# FPGA_Power.net
KiCad netlist of a schematic drawn in Altium Designer
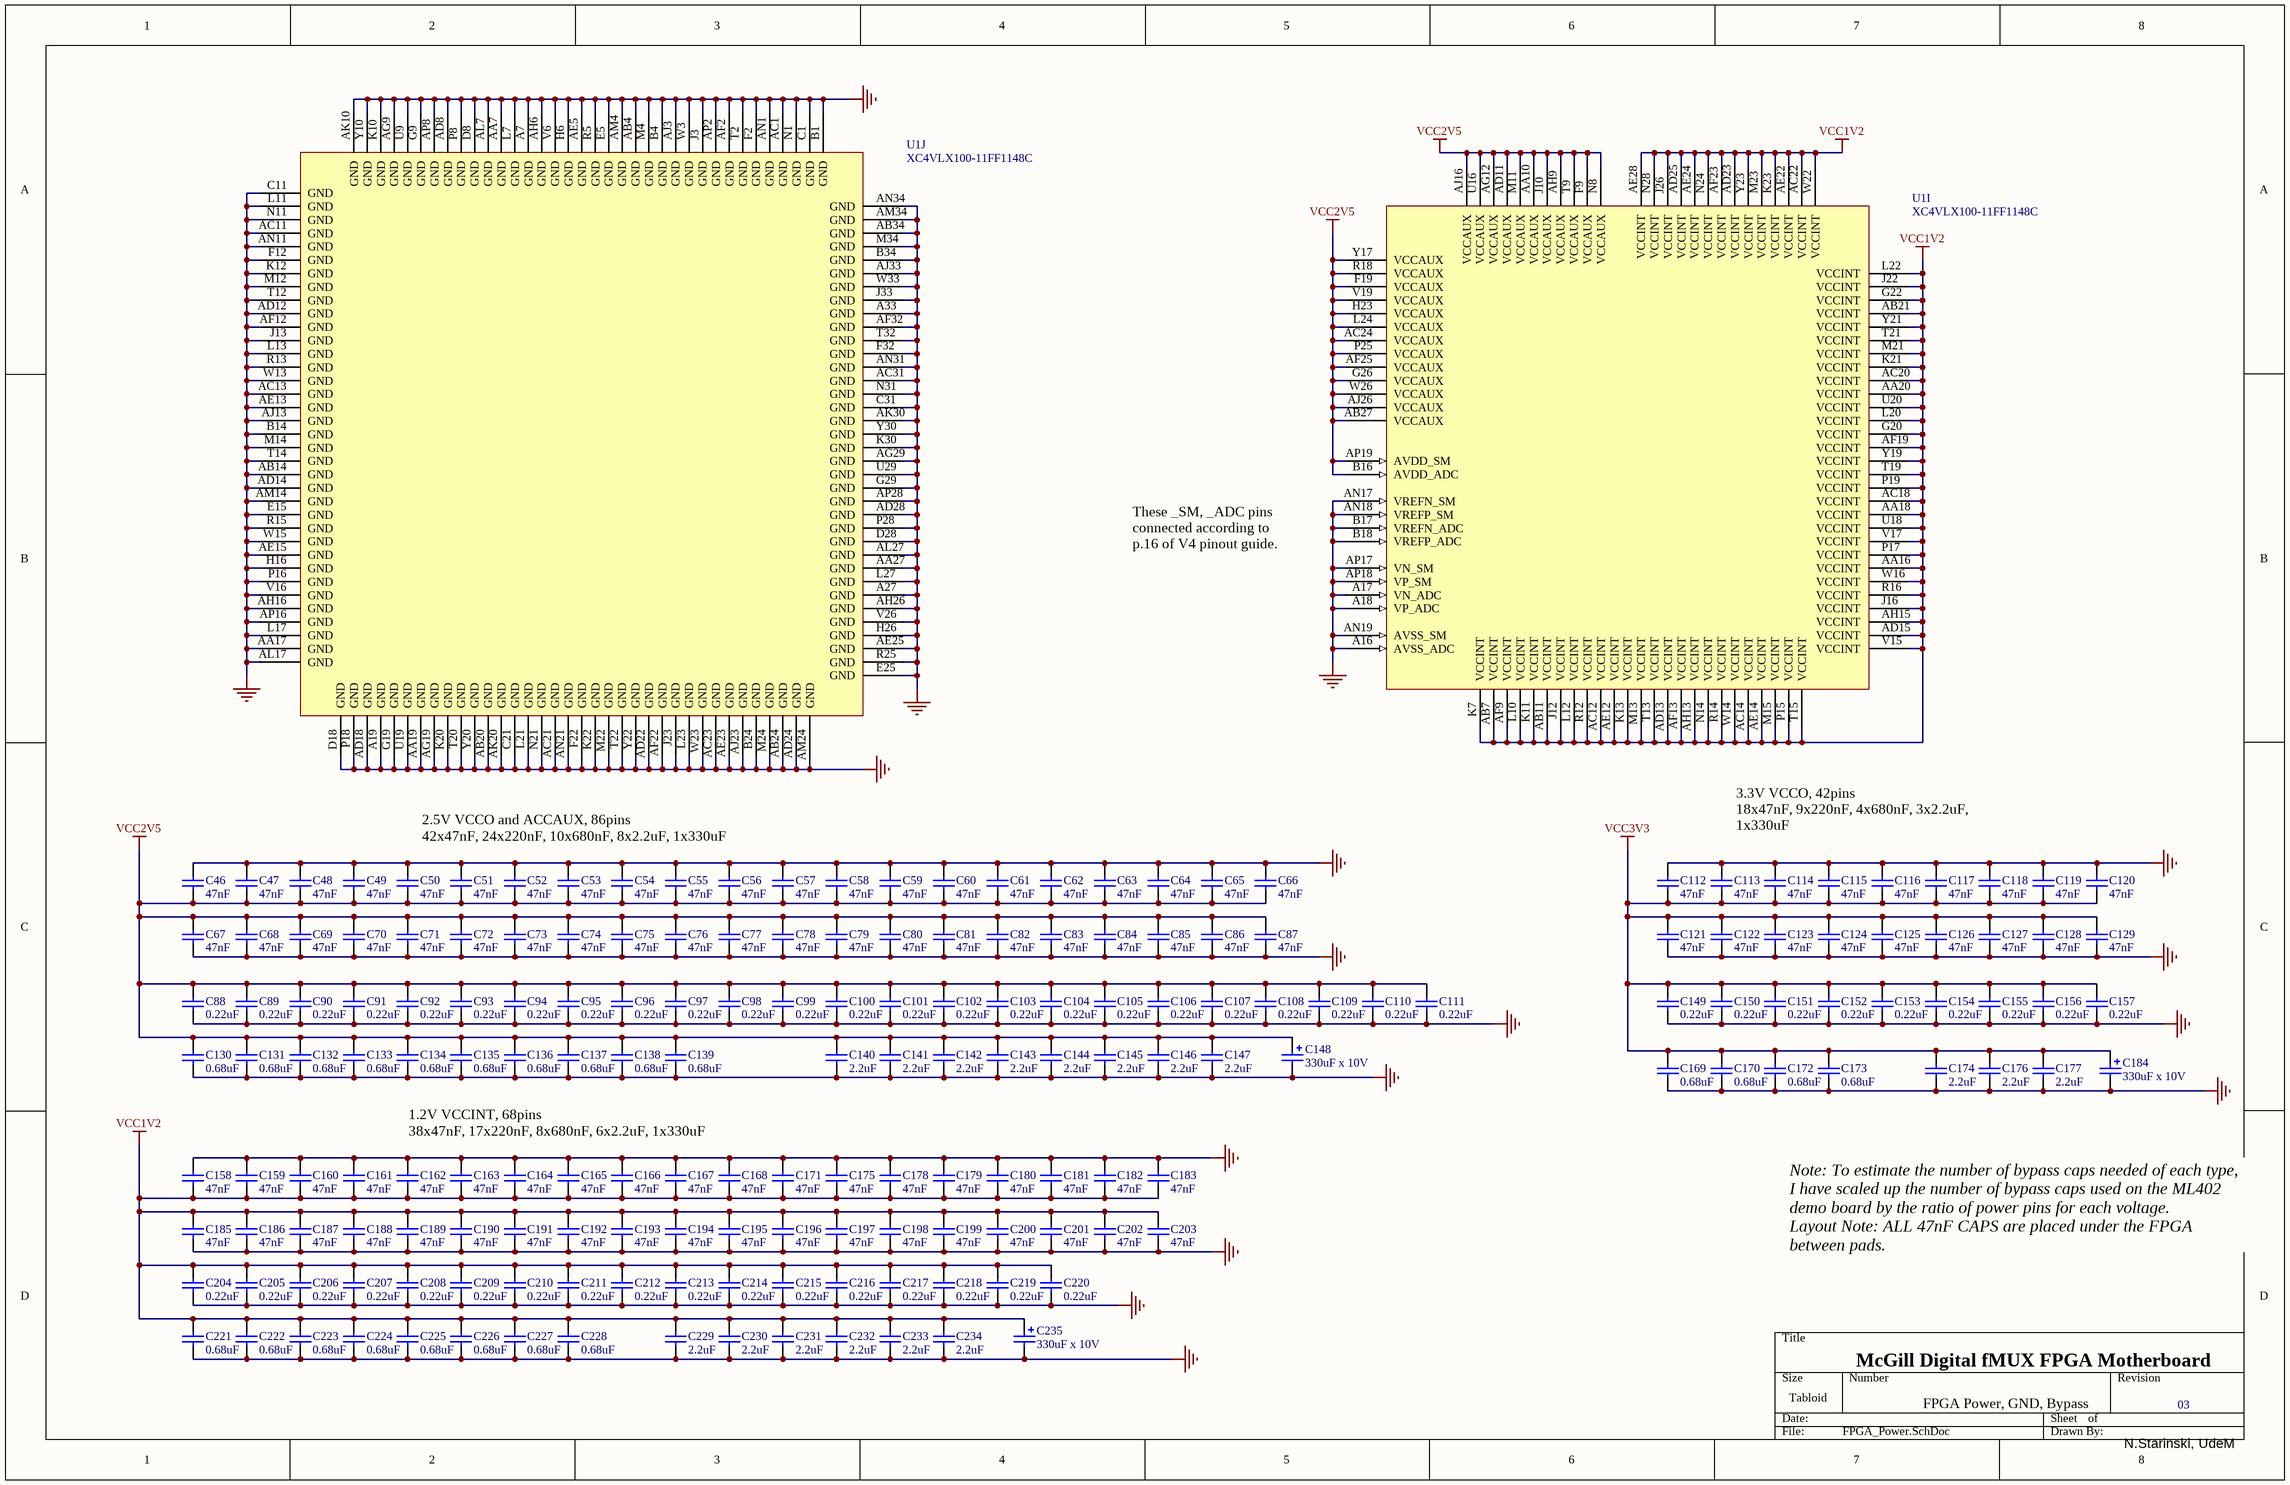
[diagram p0: FPGA_Power.SchDoc]

(export (version "E")
  (design (tool "Eeschema 10.0.6"))
  (components
    (comp (ref "C46")
      (value "47nF")
      (footprint "CC1005-0402")
      (description "Capacitor (Semiconductor SIM Model)")
      (fields (field (name "PUBLISHER") "Altium Limited"))
      (libsource (lib "Miscellaneous Devices") (part "Cap Semi"))
    )
    (comp (ref "C47")
      (value "47nF")
      (footprint "CC1005-0402")
      (description "Capacitor (Semiconductor SIM Model)")
      (fields (field (name "PUBLISHER") "Altium Limited"))
      (libsource (lib "Miscellaneous Devices") (part "Cap Semi"))
    )
    (comp (ref "C48")
      (value "47nF")
      (footprint "CC1005-0402")
      (description "Capacitor (Semiconductor SIM Model)")
      (fields (field (name "PUBLISHER") "Altium Limited"))
      (libsource (lib "Miscellaneous Devices") (part "Cap Semi"))
    )
    (comp (ref "C49")
      (value "47nF")
      (footprint "CC1005-0402")
      (description "Capacitor (Semiconductor SIM Model)")
      (fields (field (name "PUBLISHER") "Altium Limited"))
      (libsource (lib "Miscellaneous Devices") (part "Cap Semi"))
    )
    (comp (ref "C50")
      (value "47nF")
      (footprint "CC1005-0402")
      (description "Capacitor (Semiconductor SIM Model)")
      (fields (field (name "PUBLISHER") "Altium Limited"))
      (libsource (lib "Miscellaneous Devices") (part "Cap Semi"))
    )
    (comp (ref "C51")
      (value "47nF")
      (footprint "CC1005-0402")
      (description "Capacitor (Semiconductor SIM Model)")
      (fields (field (name "PUBLISHER") "Altium Limited"))
      (libsource (lib "Miscellaneous Devices") (part "Cap Semi"))
    )
    (comp (ref "C52")
      (value "47nF")
      (footprint "CC1005-0402")
      (description "Capacitor (Semiconductor SIM Model)")
      (fields (field (name "PUBLISHER") "Altium Limited"))
      (libsource (lib "Miscellaneous Devices") (part "Cap Semi"))
    )
    (comp (ref "C53")
      (value "47nF")
      (footprint "CC1005-0402")
      (description "Capacitor (Semiconductor SIM Model)")
      (fields (field (name "PUBLISHER") "Altium Limited"))
      (libsource (lib "Miscellaneous Devices") (part "Cap Semi"))
    )
    (comp (ref "C54")
      (value "47nF")
      (footprint "CC1005-0402")
      (description "Capacitor (Semiconductor SIM Model)")
      (fields (field (name "PUBLISHER") "Altium Limited"))
      (libsource (lib "Miscellaneous Devices") (part "Cap Semi"))
    )
    (comp (ref "C55")
      (value "47nF")
      (footprint "CC1005-0402")
      (description "Capacitor (Semiconductor SIM Model)")
      (fields (field (name "PUBLISHER") "Altium Limited"))
      (libsource (lib "Miscellaneous Devices") (part "Cap Semi"))
    )
    (comp (ref "C56")
      (value "47nF")
      (footprint "CC1005-0402")
      (description "Capacitor (Semiconductor SIM Model)")
      (fields (field (name "PUBLISHER") "Altium Limited"))
      (libsource (lib "Miscellaneous Devices") (part "Cap Semi"))
    )
    (comp (ref "C57")
      (value "47nF")
      (footprint "CC1005-0402")
      (description "Capacitor (Semiconductor SIM Model)")
      (fields (field (name "PUBLISHER") "Altium Limited"))
      (libsource (lib "Miscellaneous Devices") (part "Cap Semi"))
    )
    (comp (ref "C58")
      (value "47nF")
      (footprint "CC1005-0402")
      (description "Capacitor (Semiconductor SIM Model)")
      (fields (field (name "PUBLISHER") "Altium Limited"))
      (libsource (lib "Miscellaneous Devices") (part "Cap Semi"))
    )
    (comp (ref "C59")
      (value "47nF")
      (footprint "CC1005-0402")
      (description "Capacitor (Semiconductor SIM Model)")
      (fields (field (name "PUBLISHER") "Altium Limited"))
      (libsource (lib "Miscellaneous Devices") (part "Cap Semi"))
    )
    (comp (ref "C60")
      (value "47nF")
      (footprint "CC1005-0402")
      (description "Capacitor (Semiconductor SIM Model)")
      (fields (field (name "PUBLISHER") "Altium Limited"))
      (libsource (lib "Miscellaneous Devices") (part "Cap Semi"))
    )
    (comp (ref "C61")
      (value "47nF")
      (footprint "CC1005-0402")
      (description "Capacitor (Semiconductor SIM Model)")
      (fields (field (name "PUBLISHER") "Altium Limited"))
      (libsource (lib "Miscellaneous Devices") (part "Cap Semi"))
    )
    (comp (ref "C62")
      (value "47nF")
      (footprint "CC1005-0402")
      (description "Capacitor (Semiconductor SIM Model)")
      (fields (field (name "PUBLISHER") "Altium Limited"))
      (libsource (lib "Miscellaneous Devices") (part "Cap Semi"))
    )
    (comp (ref "C63")
      (value "47nF")
      (footprint "CC1005-0402")
      (description "Capacitor (Semiconductor SIM Model)")
      (fields (field (name "PUBLISHER") "Altium Limited"))
      (libsource (lib "Miscellaneous Devices") (part "Cap Semi"))
    )
    (comp (ref "C64")
      (value "47nF")
      (footprint "CC1005-0402")
      (description "Capacitor (Semiconductor SIM Model)")
      (fields (field (name "PUBLISHER") "Altium Limited"))
      (libsource (lib "Miscellaneous Devices") (part "Cap Semi"))
    )
    (comp (ref "C65")
      (value "47nF")
      (footprint "CC1005-0402")
      (description "Capacitor (Semiconductor SIM Model)")
      (fields (field (name "PUBLISHER") "Altium Limited"))
      (libsource (lib "Miscellaneous Devices") (part "Cap Semi"))
    )
    (comp (ref "C66")
      (value "47nF")
      (footprint "CC1005-0402")
      (description "Capacitor (Semiconductor SIM Model)")
      (fields (field (name "PUBLISHER") "Altium Limited"))
      (libsource (lib "Miscellaneous Devices") (part "Cap Semi"))
    )
    (comp (ref "C67")
      (value "47nF")
      (footprint "CC1005-0402")
      (description "Capacitor (Semiconductor SIM Model)")
      (fields (field (name "PUBLISHER") "Altium Limited"))
      (libsource (lib "Miscellaneous Devices") (part "Cap Semi"))
    )
    (comp (ref "C68")
      (value "47nF")
      (footprint "CC1005-0402")
      (description "Capacitor (Semiconductor SIM Model)")
      (fields (field (name "PUBLISHER") "Altium Limited"))
      (libsource (lib "Miscellaneous Devices") (part "Cap Semi"))
    )
    (comp (ref "C69")
      (value "47nF")
      (footprint "CC1005-0402")
      (description "Capacitor (Semiconductor SIM Model)")
      (fields (field (name "PUBLISHER") "Altium Limited"))
      (libsource (lib "Miscellaneous Devices") (part "Cap Semi"))
    )
    (comp (ref "C70")
      (value "47nF")
      (footprint "CC1005-0402")
      (description "Capacitor (Semiconductor SIM Model)")
      (fields (field (name "PUBLISHER") "Altium Limited"))
      (libsource (lib "Miscellaneous Devices") (part "Cap Semi"))
    )
    (comp (ref "C71")
      (value "47nF")
      (footprint "CC1005-0402")
      (description "Capacitor (Semiconductor SIM Model)")
      (fields (field (name "PUBLISHER") "Altium Limited"))
      (libsource (lib "Miscellaneous Devices") (part "Cap Semi"))
    )
    (comp (ref "C72")
      (value "47nF")
      (footprint "CC1005-0402")
      (description "Capacitor (Semiconductor SIM Model)")
      (fields (field (name "PUBLISHER") "Altium Limited"))
      (libsource (lib "Miscellaneous Devices") (part "Cap Semi"))
    )
    (comp (ref "C73")
      (value "47nF")
      (footprint "CC1005-0402")
      (description "Capacitor (Semiconductor SIM Model)")
      (fields (field (name "PUBLISHER") "Altium Limited"))
      (libsource (lib "Miscellaneous Devices") (part "Cap Semi"))
    )
    (comp (ref "C74")
      (value "47nF")
      (footprint "CC1005-0402")
      (description "Capacitor (Semiconductor SIM Model)")
      (fields (field (name "PUBLISHER") "Altium Limited"))
      (libsource (lib "Miscellaneous Devices") (part "Cap Semi"))
    )
    (comp (ref "C75")
      (value "47nF")
      (footprint "CC1005-0402")
      (description "Capacitor (Semiconductor SIM Model)")
      (fields (field (name "PUBLISHER") "Altium Limited"))
      (libsource (lib "Miscellaneous Devices") (part "Cap Semi"))
    )
    (comp (ref "C76")
      (value "47nF")
      (footprint "CC1005-0402")
      (description "Capacitor (Semiconductor SIM Model)")
      (fields (field (name "PUBLISHER") "Altium Limited"))
      (libsource (lib "Miscellaneous Devices") (part "Cap Semi"))
    )
    (comp (ref "C77")
      (value "47nF")
      (footprint "CC1005-0402")
      (description "Capacitor (Semiconductor SIM Model)")
      (fields (field (name "PUBLISHER") "Altium Limited"))
      (libsource (lib "Miscellaneous Devices") (part "Cap Semi"))
    )
    (comp (ref "C78")
      (value "47nF")
      (footprint "CC1005-0402")
      (description "Capacitor (Semiconductor SIM Model)")
      (fields (field (name "PUBLISHER") "Altium Limited"))
      (libsource (lib "Miscellaneous Devices") (part "Cap Semi"))
    )
    (comp (ref "C79")
      (value "47nF")
      (footprint "CC1005-0402")
      (description "Capacitor (Semiconductor SIM Model)")
      (fields (field (name "PUBLISHER") "Altium Limited"))
      (libsource (lib "Miscellaneous Devices") (part "Cap Semi"))
    )
    (comp (ref "C80")
      (value "47nF")
      (footprint "CC1005-0402")
      (description "Capacitor (Semiconductor SIM Model)")
      (fields (field (name "PUBLISHER") "Altium Limited"))
      (libsource (lib "Miscellaneous Devices") (part "Cap Semi"))
    )
    (comp (ref "C81")
      (value "47nF")
      (footprint "CC1005-0402")
      (description "Capacitor (Semiconductor SIM Model)")
      (fields (field (name "PUBLISHER") "Altium Limited"))
      (libsource (lib "Miscellaneous Devices") (part "Cap Semi"))
    )
    (comp (ref "C82")
      (value "47nF")
      (footprint "CC1005-0402")
      (description "Capacitor (Semiconductor SIM Model)")
      (fields (field (name "PUBLISHER") "Altium Limited"))
      (libsource (lib "Miscellaneous Devices") (part "Cap Semi"))
    )
    (comp (ref "C83")
      (value "47nF")
      (footprint "CC1005-0402")
      (description "Capacitor (Semiconductor SIM Model)")
      (fields (field (name "PUBLISHER") "Altium Limited"))
      (libsource (lib "Miscellaneous Devices") (part "Cap Semi"))
    )
    (comp (ref "C84")
      (value "47nF")
      (footprint "CC1005-0402")
      (description "Capacitor (Semiconductor SIM Model)")
      (fields (field (name "PUBLISHER") "Altium Limited"))
      (libsource (lib "Miscellaneous Devices") (part "Cap Semi"))
    )
    (comp (ref "C85")
      (value "47nF")
      (footprint "CC1005-0402")
      (description "Capacitor (Semiconductor SIM Model)")
      (fields (field (name "PUBLISHER") "Altium Limited"))
      (libsource (lib "Miscellaneous Devices") (part "Cap Semi"))
    )
    (comp (ref "C86")
      (value "47nF")
      (footprint "CC1005-0402")
      (description "Capacitor (Semiconductor SIM Model)")
      (fields (field (name "PUBLISHER") "Altium Limited"))
      (libsource (lib "Miscellaneous Devices") (part "Cap Semi"))
    )
    (comp (ref "C87")
      (value "47nF")
      (footprint "CC1005-0402")
      (description "Capacitor (Semiconductor SIM Model)")
      (fields (field (name "PUBLISHER") "Altium Limited"))
      (libsource (lib "Miscellaneous Devices") (part "Cap Semi"))
    )
    (comp (ref "C88")
      (value "0.22uF")
      (footprint "CC1608-0603")
      (description "Capacitor (Semiconductor SIM Model)")
      (fields (field (name "PUBLISHER") "Altium Limited"))
      (libsource (lib "Miscellaneous Devices") (part "Cap Semi"))
    )
    (comp (ref "C89")
      (value "0.22uF")
      (footprint "CC1608-0603")
      (description "Capacitor (Semiconductor SIM Model)")
      (fields (field (name "PUBLISHER") "Altium Limited"))
      (libsource (lib "Miscellaneous Devices") (part "Cap Semi"))
    )
    (comp (ref "C90")
      (value "0.22uF")
      (footprint "CC1608-0603")
      (description "Capacitor (Semiconductor SIM Model)")
      (fields (field (name "PUBLISHER") "Altium Limited"))
      (libsource (lib "Miscellaneous Devices") (part "Cap Semi"))
    )
    (comp (ref "C91")
      (value "0.22uF")
      (footprint "CC1608-0603")
      (description "Capacitor (Semiconductor SIM Model)")
      (fields (field (name "PUBLISHER") "Altium Limited"))
      (libsource (lib "Miscellaneous Devices") (part "Cap Semi"))
    )
    (comp (ref "C92")
      (value "0.22uF")
      (footprint "CC1608-0603")
      (description "Capacitor (Semiconductor SIM Model)")
      (fields (field (name "PUBLISHER") "Altium Limited"))
      (libsource (lib "Miscellaneous Devices") (part "Cap Semi"))
    )
    (comp (ref "C93")
      (value "0.22uF")
      (footprint "CC1608-0603")
      (description "Capacitor (Semiconductor SIM Model)")
      (fields (field (name "PUBLISHER") "Altium Limited"))
      (libsource (lib "Miscellaneous Devices") (part "Cap Semi"))
    )
    (comp (ref "C94")
      (value "0.22uF")
      (footprint "CC1608-0603")
      (description "Capacitor (Semiconductor SIM Model)")
      (fields (field (name "PUBLISHER") "Altium Limited"))
      (libsource (lib "Miscellaneous Devices") (part "Cap Semi"))
    )
    (comp (ref "C95")
      (value "0.22uF")
      (footprint "CC1608-0603")
      (description "Capacitor (Semiconductor SIM Model)")
      (fields (field (name "PUBLISHER") "Altium Limited"))
      (libsource (lib "Miscellaneous Devices") (part "Cap Semi"))
    )
    (comp (ref "C96")
      (value "0.22uF")
      (footprint "CC1608-0603")
      (description "Capacitor (Semiconductor SIM Model)")
      (fields (field (name "PUBLISHER") "Altium Limited"))
      (libsource (lib "Miscellaneous Devices") (part "Cap Semi"))
    )
    (comp (ref "C97")
      (value "0.22uF")
      (footprint "CC1608-0603")
      (description "Capacitor (Semiconductor SIM Model)")
      (fields (field (name "PUBLISHER") "Altium Limited"))
      (libsource (lib "Miscellaneous Devices") (part "Cap Semi"))
    )
    (comp (ref "C98")
      (value "0.22uF")
      (footprint "CC1608-0603")
      (description "Capacitor (Semiconductor SIM Model)")
      (fields (field (name "PUBLISHER") "Altium Limited"))
      (libsource (lib "Miscellaneous Devices") (part "Cap Semi"))
    )
    (comp (ref "C99")
      (value "0.22uF")
      (footprint "CC1608-0603")
      (description "Capacitor (Semiconductor SIM Model)")
      (fields (field (name "PUBLISHER") "Altium Limited"))
      (libsource (lib "Miscellaneous Devices") (part "Cap Semi"))
    )
    (comp (ref "C100")
      (value "0.22uF")
      (footprint "CC1608-0603")
      (description "Capacitor (Semiconductor SIM Model)")
      (fields (field (name "PUBLISHER") "Altium Limited"))
      (libsource (lib "Miscellaneous Devices") (part "Cap Semi"))
    )
    (comp (ref "C101")
      (value "0.22uF")
      (footprint "CC1608-0603")
      (description "Capacitor (Semiconductor SIM Model)")
      (fields (field (name "PUBLISHER") "Altium Limited"))
      (libsource (lib "Miscellaneous Devices") (part "Cap Semi"))
    )
    (comp (ref "C102")
      (value "0.22uF")
      (footprint "CC1608-0603")
      (description "Capacitor (Semiconductor SIM Model)")
      (fields (field (name "PUBLISHER") "Altium Limited"))
      (libsource (lib "Miscellaneous Devices") (part "Cap Semi"))
    )
    (comp (ref "C103")
      (value "0.22uF")
      (footprint "CC1608-0603")
      (description "Capacitor (Semiconductor SIM Model)")
      (fields (field (name "PUBLISHER") "Altium Limited"))
      (libsource (lib "Miscellaneous Devices") (part "Cap Semi"))
    )
    (comp (ref "C104")
      (value "0.22uF")
      (footprint "CC1608-0603")
      (description "Capacitor (Semiconductor SIM Model)")
      (fields (field (name "PUBLISHER") "Altium Limited"))
      (libsource (lib "Miscellaneous Devices") (part "Cap Semi"))
    )
    (comp (ref "C105")
      (value "0.22uF")
      (footprint "CC1608-0603")
      (description "Capacitor (Semiconductor SIM Model)")
      (fields (field (name "PUBLISHER") "Altium Limited"))
      (libsource (lib "Miscellaneous Devices") (part "Cap Semi"))
    )
    (comp (ref "C106")
      (value "0.22uF")
      (footprint "CC1608-0603")
      (description "Capacitor (Semiconductor SIM Model)")
      (fields (field (name "PUBLISHER") "Altium Limited"))
      (libsource (lib "Miscellaneous Devices") (part "Cap Semi"))
    )
    (comp (ref "C107")
      (value "0.22uF")
      (footprint "CC1608-0603")
      (description "Capacitor (Semiconductor SIM Model)")
      (fields (field (name "PUBLISHER") "Altium Limited"))
      (libsource (lib "Miscellaneous Devices") (part "Cap Semi"))
    )
    (comp (ref "C108")
      (value "0.22uF")
      (footprint "CC1608-0603")
      (description "Capacitor (Semiconductor SIM Model)")
      (fields (field (name "PUBLISHER") "Altium Limited"))
      (libsource (lib "Miscellaneous Devices") (part "Cap Semi"))
    )
    (comp (ref "C109")
      (value "0.22uF")
      (footprint "CC1608-0603")
      (description "Capacitor (Semiconductor SIM Model)")
      (fields (field (name "PUBLISHER") "Altium Limited"))
      (libsource (lib "Miscellaneous Devices") (part "Cap Semi"))
    )
    (comp (ref "C110")
      (value "0.22uF")
      (footprint "CC1608-0603")
      (description "Capacitor (Semiconductor SIM Model)")
      (fields (field (name "PUBLISHER") "Altium Limited"))
      (libsource (lib "Miscellaneous Devices") (part "Cap Semi"))
    )
    (comp (ref "C111")
      (value "0.22uF")
      (footprint "CC1608-0603")
      (description "Capacitor (Semiconductor SIM Model)")
      (fields (field (name "PUBLISHER") "Altium Limited"))
      (libsource (lib "Miscellaneous Devices") (part "Cap Semi"))
    )
    (comp (ref "C112")
      (value "47nF")
      (footprint "CC1005-0402")
      (description "Capacitor (Semiconductor SIM Model)")
      (fields (field (name "PUBLISHER") "Altium Limited"))
      (libsource (lib "Miscellaneous Devices") (part "Cap Semi"))
    )
    (comp (ref "C113")
      (value "47nF")
      (footprint "CC1005-0402")
      (description "Capacitor (Semiconductor SIM Model)")
      (fields (field (name "PUBLISHER") "Altium Limited"))
      (libsource (lib "Miscellaneous Devices") (part "Cap Semi"))
    )
    (comp (ref "C114")
      (value "47nF")
      (footprint "CC1005-0402")
      (description "Capacitor (Semiconductor SIM Model)")
      (fields (field (name "PUBLISHER") "Altium Limited"))
      (libsource (lib "Miscellaneous Devices") (part "Cap Semi"))
    )
    (comp (ref "C115")
      (value "47nF")
      (footprint "CC1005-0402")
      (description "Capacitor (Semiconductor SIM Model)")
      (fields (field (name "PUBLISHER") "Altium Limited"))
      (libsource (lib "Miscellaneous Devices") (part "Cap Semi"))
    )
    (comp (ref "C116")
      (value "47nF")
      (footprint "CC1005-0402")
      (description "Capacitor (Semiconductor SIM Model)")
      (fields (field (name "PUBLISHER") "Altium Limited"))
      (libsource (lib "Miscellaneous Devices") (part "Cap Semi"))
    )
    (comp (ref "C117")
      (value "47nF")
      (footprint "CC1005-0402")
      (description "Capacitor (Semiconductor SIM Model)")
      (fields (field (name "PUBLISHER") "Altium Limited"))
      (libsource (lib "Miscellaneous Devices") (part "Cap Semi"))
    )
    (comp (ref "C118")
      (value "47nF")
      (footprint "CC1005-0402")
      (description "Capacitor (Semiconductor SIM Model)")
      (fields (field (name "PUBLISHER") "Altium Limited"))
      (libsource (lib "Miscellaneous Devices") (part "Cap Semi"))
    )
    (comp (ref "C119")
      (value "47nF")
      (footprint "CC1005-0402")
      (description "Capacitor (Semiconductor SIM Model)")
      (fields (field (name "PUBLISHER") "Altium Limited"))
      (libsource (lib "Miscellaneous Devices") (part "Cap Semi"))
    )
    (comp (ref "C120")
      (value "47nF")
      (footprint "CC1005-0402")
      (description "Capacitor (Semiconductor SIM Model)")
      (fields (field (name "PUBLISHER") "Altium Limited"))
      (libsource (lib "Miscellaneous Devices") (part "Cap Semi"))
    )
    (comp (ref "C121")
      (value "47nF")
      (footprint "CC1005-0402")
      (description "Capacitor (Semiconductor SIM Model)")
      (fields (field (name "PUBLISHER") "Altium Limited"))
      (libsource (lib "Miscellaneous Devices") (part "Cap Semi"))
    )
    (comp (ref "C122")
      (value "47nF")
      (footprint "CC1005-0402")
      (description "Capacitor (Semiconductor SIM Model)")
      (fields (field (name "PUBLISHER") "Altium Limited"))
      (libsource (lib "Miscellaneous Devices") (part "Cap Semi"))
    )
    (comp (ref "C123")
      (value "47nF")
      (footprint "CC1005-0402")
      (description "Capacitor (Semiconductor SIM Model)")
      (fields (field (name "PUBLISHER") "Altium Limited"))
      (libsource (lib "Miscellaneous Devices") (part "Cap Semi"))
    )
    (comp (ref "C124")
      (value "47nF")
      (footprint "CC1005-0402")
      (description "Capacitor (Semiconductor SIM Model)")
      (fields (field (name "PUBLISHER") "Altium Limited"))
      (libsource (lib "Miscellaneous Devices") (part "Cap Semi"))
    )
    (comp (ref "C125")
      (value "47nF")
      (footprint "CC1005-0402")
      (description "Capacitor (Semiconductor SIM Model)")
      (fields (field (name "PUBLISHER") "Altium Limited"))
      (libsource (lib "Miscellaneous Devices") (part "Cap Semi"))
    )
    (comp (ref "C126")
      (value "47nF")
      (footprint "CC1005-0402")
      (description "Capacitor (Semiconductor SIM Model)")
      (fields (field (name "PUBLISHER") "Altium Limited"))
      (libsource (lib "Miscellaneous Devices") (part "Cap Semi"))
    )
    (comp (ref "C127")
      (value "47nF")
      (footprint "CC1005-0402")
      (description "Capacitor (Semiconductor SIM Model)")
      (fields (field (name "PUBLISHER") "Altium Limited"))
      (libsource (lib "Miscellaneous Devices") (part "Cap Semi"))
    )
    (comp (ref "C128")
      (value "47nF")
      (footprint "CC1005-0402")
      (description "Capacitor (Semiconductor SIM Model)")
      (fields (field (name "PUBLISHER") "Altium Limited"))
      (libsource (lib "Miscellaneous Devices") (part "Cap Semi"))
    )
    (comp (ref "C129")
      (value "47nF")
      (footprint "CC1005-0402")
      (description "Capacitor (Semiconductor SIM Model)")
      (fields (field (name "PUBLISHER") "Altium Limited"))
      (libsource (lib "Miscellaneous Devices") (part "Cap Semi"))
    )
    (comp (ref "C130")
      (value "0.68uF")
      (footprint "CC3216-1206")
      (description "Capacitor (Semiconductor SIM Model)")
      (fields (field (name "PUBLISHER") "Altium Limited"))
      (libsource (lib "Miscellaneous Devices") (part "Cap Semi"))
    )
    (comp (ref "C131")
      (value "0.68uF")
      (footprint "CC3216-1206")
      (description "Capacitor (Semiconductor SIM Model)")
      (fields (field (name "PUBLISHER") "Altium Limited"))
      (libsource (lib "Miscellaneous Devices") (part "Cap Semi"))
    )
    (comp (ref "C132")
      (value "0.68uF")
      (footprint "CC3216-1206")
      (description "Capacitor (Semiconductor SIM Model)")
      (fields (field (name "PUBLISHER") "Altium Limited"))
      (libsource (lib "Miscellaneous Devices") (part "Cap Semi"))
    )
    (comp (ref "C133")
      (value "0.68uF")
      (footprint "CC3216-1206")
      (description "Capacitor (Semiconductor SIM Model)")
      (fields (field (name "PUBLISHER") "Altium Limited"))
      (libsource (lib "Miscellaneous Devices") (part "Cap Semi"))
    )
    (comp (ref "C134")
      (value "0.68uF")
      (footprint "CC3216-1206")
      (description "Capacitor (Semiconductor SIM Model)")
      (fields (field (name "PUBLISHER") "Altium Limited"))
      (libsource (lib "Miscellaneous Devices") (part "Cap Semi"))
    )
    (comp (ref "C135")
      (value "0.68uF")
      (footprint "CC3216-1206")
      (description "Capacitor (Semiconductor SIM Model)")
      (fields (field (name "PUBLISHER") "Altium Limited"))
      (libsource (lib "Miscellaneous Devices") (part "Cap Semi"))
    )
    (comp (ref "C136")
      (value "0.68uF")
      (footprint "CC3216-1206")
      (description "Capacitor (Semiconductor SIM Model)")
      (fields (field (name "PUBLISHER") "Altium Limited"))
      (libsource (lib "Miscellaneous Devices") (part "Cap Semi"))
    )
    (comp (ref "C137")
      (value "0.68uF")
      (footprint "CC3216-1206")
      (description "Capacitor (Semiconductor SIM Model)")
      (fields (field (name "PUBLISHER") "Altium Limited"))
      (libsource (lib "Miscellaneous Devices") (part "Cap Semi"))
    )
    (comp (ref "C138")
      (value "0.68uF")
      (footprint "CC3216-1206")
      (description "Capacitor (Semiconductor SIM Model)")
      (fields (field (name "PUBLISHER") "Altium Limited"))
      (libsource (lib "Miscellaneous Devices") (part "Cap Semi"))
    )
    (comp (ref "C139")
      (value "0.68uF")
      (footprint "CC3216-1206")
      (description "Capacitor (Semiconductor SIM Model)")
      (fields (field (name "PUBLISHER") "Altium Limited"))
      (libsource (lib "Miscellaneous Devices") (part "Cap Semi"))
    )
    (comp (ref "C140")
      (value "2.2uF")
      (footprint "CC3216-1206")
      (description "Capacitor (Semiconductor SIM Model)")
      (fields (field (name "PUBLISHER") "Altium Limited"))
      (libsource (lib "Miscellaneous Devices") (part "Cap Semi"))
    )
    (comp (ref "C141")
      (value "2.2uF")
      (footprint "CC3216-1206")
      (description "Capacitor (Semiconductor SIM Model)")
      (fields (field (name "PUBLISHER") "Altium Limited"))
      (libsource (lib "Miscellaneous Devices") (part "Cap Semi"))
    )
    (comp (ref "C142")
      (value "2.2uF")
      (footprint "CC3216-1206")
      (description "Capacitor (Semiconductor SIM Model)")
      (fields (field (name "PUBLISHER") "Altium Limited"))
      (libsource (lib "Miscellaneous Devices") (part "Cap Semi"))
    )
    (comp (ref "C143")
      (value "2.2uF")
      (footprint "CC3216-1206")
      (description "Capacitor (Semiconductor SIM Model)")
      (fields (field (name "PUBLISHER") "Altium Limited"))
      (libsource (lib "Miscellaneous Devices") (part "Cap Semi"))
    )
    (comp (ref "C144")
      (value "2.2uF")
      (footprint "CC3216-1206")
      (description "Capacitor (Semiconductor SIM Model)")
      (fields (field (name "PUBLISHER") "Altium Limited"))
      (libsource (lib "Miscellaneous Devices") (part "Cap Semi"))
    )
    (comp (ref "C145")
      (value "2.2uF")
      (footprint "CC3216-1206")
      (description "Capacitor (Semiconductor SIM Model)")
      (fields (field (name "PUBLISHER") "Altium Limited"))
      (libsource (lib "Miscellaneous Devices") (part "Cap Semi"))
    )
    (comp (ref "C146")
      (value "2.2uF")
      (footprint "CC3216-1206")
      (description "Capacitor (Semiconductor SIM Model)")
      (fields (field (name "PUBLISHER") "Altium Limited"))
      (libsource (lib "Miscellaneous Devices") (part "Cap Semi"))
    )
    (comp (ref "C147")
      (value "2.2uF")
      (footprint "CC3216-1206")
      (description "Capacitor (Semiconductor SIM Model)")
      (fields (field (name "PUBLISHER") "Altium Limited"))
      (libsource (lib "Miscellaneous Devices") (part "Cap Semi"))
    )
    (comp (ref "C148")
      (value "330uF x 10V")
      (footprint "CC7343-31_Dsize")
      (description "CAP TANTD TPSD337K010R0100")
      (fields (field (name "PUBLISHER") "Altium Limited"))
      (libsource (lib "Miscellaneous Devices") (part "Cap Pol3"))
    )
    (comp (ref "C149")
      (value "0.22uF")
      (footprint "CC1608-0603")
      (description "Capacitor (Semiconductor SIM Model)")
      (fields (field (name "PUBLISHER") "Altium Limited"))
      (libsource (lib "Miscellaneous Devices") (part "Cap Semi"))
    )
    (comp (ref "C150")
      (value "0.22uF")
      (footprint "CC1608-0603")
      (description "Capacitor (Semiconductor SIM Model)")
      (fields (field (name "PUBLISHER") "Altium Limited"))
      (libsource (lib "Miscellaneous Devices") (part "Cap Semi"))
    )
    (comp (ref "C151")
      (value "0.22uF")
      (footprint "CC1608-0603")
      (description "Capacitor (Semiconductor SIM Model)")
      (fields (field (name "PUBLISHER") "Altium Limited"))
      (libsource (lib "Miscellaneous Devices") (part "Cap Semi"))
    )
    (comp (ref "C152")
      (value "0.22uF")
      (footprint "CC1608-0603")
      (description "Capacitor (Semiconductor SIM Model)")
      (fields (field (name "PUBLISHER") "Altium Limited"))
      (libsource (lib "Miscellaneous Devices") (part "Cap Semi"))
    )
    (comp (ref "C153")
      (value "0.22uF")
      (footprint "CC1608-0603")
      (description "Capacitor (Semiconductor SIM Model)")
      (fields (field (name "PUBLISHER") "Altium Limited"))
      (libsource (lib "Miscellaneous Devices") (part "Cap Semi"))
    )
    (comp (ref "C154")
      (value "0.22uF")
      (footprint "CC1608-0603")
      (description "Capacitor (Semiconductor SIM Model)")
      (fields (field (name "PUBLISHER") "Altium Limited"))
      (libsource (lib "Miscellaneous Devices") (part "Cap Semi"))
    )
    (comp (ref "C155")
      (value "0.22uF")
      (footprint "CC1608-0603")
      (description "Capacitor (Semiconductor SIM Model)")
      (fields (field (name "PUBLISHER") "Altium Limited"))
      (libsource (lib "Miscellaneous Devices") (part "Cap Semi"))
    )
    (comp (ref "C156")
      (value "0.22uF")
      (footprint "CC1608-0603")
      (description "Capacitor (Semiconductor SIM Model)")
      (fields (field (name "PUBLISHER") "Altium Limited"))
      (libsource (lib "Miscellaneous Devices") (part "Cap Semi"))
    )
    (comp (ref "C157")
      (value "0.22uF")
      (footprint "CC1608-0603")
      (description "Capacitor (Semiconductor SIM Model)")
      (fields (field (name "PUBLISHER") "Altium Limited"))
      (libsource (lib "Miscellaneous Devices") (part "Cap Semi"))
    )
    (comp (ref "C158")
      (value "47nF")
      (footprint "CC1005-0402")
      (description "Capacitor (Semiconductor SIM Model)")
      (fields (field (name "PUBLISHER") "Altium Limited"))
      (libsource (lib "Miscellaneous Devices") (part "Cap Semi"))
    )
    (comp (ref "C159")
      (value "47nF")
      (footprint "CC1005-0402")
      (description "Capacitor (Semiconductor SIM Model)")
      (fields (field (name "PUBLISHER") "Altium Limited"))
      (libsource (lib "Miscellaneous Devices") (part "Cap Semi"))
    )
    (comp (ref "C160")
      (value "47nF")
      (footprint "CC1005-0402")
      (description "Capacitor (Semiconductor SIM Model)")
      (fields (field (name "PUBLISHER") "Altium Limited"))
      (libsource (lib "Miscellaneous Devices") (part "Cap Semi"))
    )
    (comp (ref "C161")
      (value "47nF")
      (footprint "CC1005-0402")
      (description "Capacitor (Semiconductor SIM Model)")
      (fields (field (name "PUBLISHER") "Altium Limited"))
      (libsource (lib "Miscellaneous Devices") (part "Cap Semi"))
    )
    (comp (ref "C162")
      (value "47nF")
      (footprint "CC1005-0402")
      (description "Capacitor (Semiconductor SIM Model)")
      (fields (field (name "PUBLISHER") "Altium Limited"))
      (libsource (lib "Miscellaneous Devices") (part "Cap Semi"))
    )
    (comp (ref "C163")
      (value "47nF")
      (footprint "CC1005-0402")
      (description "Capacitor (Semiconductor SIM Model)")
      (fields (field (name "PUBLISHER") "Altium Limited"))
      (libsource (lib "Miscellaneous Devices") (part "Cap Semi"))
    )
    (comp (ref "C164")
      (value "47nF")
      (footprint "CC1005-0402")
      (description "Capacitor (Semiconductor SIM Model)")
      (fields (field (name "PUBLISHER") "Altium Limited"))
      (libsource (lib "Miscellaneous Devices") (part "Cap Semi"))
    )
    (comp (ref "C165")
      (value "47nF")
      (footprint "CC1005-0402")
      (description "Capacitor (Semiconductor SIM Model)")
      (fields (field (name "PUBLISHER") "Altium Limited"))
      (libsource (lib "Miscellaneous Devices") (part "Cap Semi"))
    )
    (comp (ref "C166")
      (value "47nF")
      (footprint "CC1005-0402")
      (description "Capacitor (Semiconductor SIM Model)")
      (fields (field (name "PUBLISHER") "Altium Limited"))
      (libsource (lib "Miscellaneous Devices") (part "Cap Semi"))
    )
    (comp (ref "C167")
      (value "47nF")
      (footprint "CC1005-0402")
      (description "Capacitor (Semiconductor SIM Model)")
      (fields (field (name "PUBLISHER") "Altium Limited"))
      (libsource (lib "Miscellaneous Devices") (part "Cap Semi"))
    )
    (comp (ref "C168")
      (value "47nF")
      (footprint "CC1005-0402")
      (description "Capacitor (Semiconductor SIM Model)")
      (fields (field (name "PUBLISHER") "Altium Limited"))
      (libsource (lib "Miscellaneous Devices") (part "Cap Semi"))
    )
    (comp (ref "C169")
      (value "0.68uF")
      (footprint "CC3216-1206")
      (description "Capacitor (Semiconductor SIM Model)")
      (fields (field (name "PUBLISHER") "Altium Limited"))
      (libsource (lib "Miscellaneous Devices") (part "Cap Semi"))
    )
    (comp (ref "C170")
      (value "0.68uF")
      (footprint "CC3216-1206")
      (description "Capacitor (Semiconductor SIM Model)")
      (fields (field (name "PUBLISHER") "Altium Limited"))
      (libsource (lib "Miscellaneous Devices") (part "Cap Semi"))
    )
    (comp (ref "C171")
      (value "47nF")
      (footprint "CC1005-0402")
      (description "Capacitor (Semiconductor SIM Model)")
      (fields (field (name "PUBLISHER") "Altium Limited"))
      (libsource (lib "Miscellaneous Devices") (part "Cap Semi"))
    )
    (comp (ref "C172")
      (value "0.68uF")
      (footprint "CC3216-1206")
      (description "Capacitor (Semiconductor SIM Model)")
      (fields (field (name "PUBLISHER") "Altium Limited"))
      (libsource (lib "Miscellaneous Devices") (part "Cap Semi"))
    )
    (comp (ref "C173")
      (value "0.68uF")
      (footprint "CC3216-1206")
      (description "Capacitor (Semiconductor SIM Model)")
      (fields (field (name "PUBLISHER") "Altium Limited"))
      (libsource (lib "Miscellaneous Devices") (part "Cap Semi"))
    )
    (comp (ref "C174")
      (value "2.2uF")
      (footprint "CC3216-1206")
      (description "Capacitor (Semiconductor SIM Model)")
      (fields (field (name "PUBLISHER") "Altium Limited"))
      (libsource (lib "Miscellaneous Devices") (part "Cap Semi"))
    )
    (comp (ref "C175")
      (value "47nF")
      (footprint "CC1005-0402")
      (description "Capacitor (Semiconductor SIM Model)")
      (fields (field (name "PUBLISHER") "Altium Limited"))
      (libsource (lib "Miscellaneous Devices") (part "Cap Semi"))
    )
    (comp (ref "C176")
      (value "2.2uF")
      (footprint "CC3216-1206")
      (description "Capacitor (Semiconductor SIM Model)")
      (fields (field (name "PUBLISHER") "Altium Limited"))
      (libsource (lib "Miscellaneous Devices") (part "Cap Semi"))
    )
    (comp (ref "C177")
      (value "2.2uF")
      (footprint "CC3216-1206")
      (description "Capacitor (Semiconductor SIM Model)")
      (fields (field (name "PUBLISHER") "Altium Limited"))
      (libsource (lib "Miscellaneous Devices") (part "Cap Semi"))
    )
    (comp (ref "C178")
      (value "47nF")
      (footprint "CC1005-0402")
      (description "Capacitor (Semiconductor SIM Model)")
      (fields (field (name "PUBLISHER") "Altium Limited"))
      (libsource (lib "Miscellaneous Devices") (part "Cap Semi"))
    )
    (comp (ref "C179")
      (value "47nF")
      (footprint "CC1005-0402")
      (description "Capacitor (Semiconductor SIM Model)")
      (fields (field (name "PUBLISHER") "Altium Limited"))
      (libsource (lib "Miscellaneous Devices") (part "Cap Semi"))
    )
    (comp (ref "C180")
      (value "47nF")
      (footprint "CC1005-0402")
      (description "Capacitor (Semiconductor SIM Model)")
      (fields (field (name "PUBLISHER") "Altium Limited"))
      (libsource (lib "Miscellaneous Devices") (part "Cap Semi"))
    )
    (comp (ref "C181")
      (value "47nF")
      (footprint "CC1005-0402")
      (description "Capacitor (Semiconductor SIM Model)")
      (fields (field (name "PUBLISHER") "Altium Limited"))
      (libsource (lib "Miscellaneous Devices") (part "Cap Semi"))
    )
    (comp (ref "C182")
      (value "47nF")
      (footprint "CC1005-0402")
      (description "Capacitor (Semiconductor SIM Model)")
      (fields (field (name "PUBLISHER") "Altium Limited"))
      (libsource (lib "Miscellaneous Devices") (part "Cap Semi"))
    )
    (comp (ref "C183")
      (value "47nF")
      (footprint "CC1005-0402")
      (description "Capacitor (Semiconductor SIM Model)")
      (fields (field (name "PUBLISHER") "Altium Limited"))
      (libsource (lib "Miscellaneous Devices") (part "Cap Semi"))
    )
    (comp (ref "C184")
      (value "330uF x 10V")
      (footprint "CC7343-31_Dsize")
      (description "CAP TANTD TPSD337K010R0100")
      (fields (field (name "PUBLISHER") "Altium Limited"))
      (libsource (lib "Miscellaneous Devices") (part "Cap Pol3"))
    )
    (comp (ref "C185")
      (value "47nF")
      (footprint "CC1005-0402")
      (description "Capacitor (Semiconductor SIM Model)")
      (fields (field (name "PUBLISHER") "Altium Limited"))
      (libsource (lib "Miscellaneous Devices") (part "Cap Semi"))
    )
    (comp (ref "C186")
      (value "47nF")
      (footprint "CC1005-0402")
      (description "Capacitor (Semiconductor SIM Model)")
      (fields (field (name "PUBLISHER") "Altium Limited"))
      (libsource (lib "Miscellaneous Devices") (part "Cap Semi"))
    )
    (comp (ref "C187")
      (value "47nF")
      (footprint "CC1005-0402")
      (description "Capacitor (Semiconductor SIM Model)")
      (fields (field (name "PUBLISHER") "Altium Limited"))
      (libsource (lib "Miscellaneous Devices") (part "Cap Semi"))
    )
    (comp (ref "C188")
      (value "47nF")
      (footprint "CC1005-0402")
      (description "Capacitor (Semiconductor SIM Model)")
      (fields (field (name "PUBLISHER") "Altium Limited"))
      (libsource (lib "Miscellaneous Devices") (part "Cap Semi"))
    )
    (comp (ref "C189")
      (value "47nF")
      (footprint "CC1005-0402")
      (description "Capacitor (Semiconductor SIM Model)")
      (fields (field (name "PUBLISHER") "Altium Limited"))
      (libsource (lib "Miscellaneous Devices") (part "Cap Semi"))
    )
    (comp (ref "C190")
      (value "47nF")
      (footprint "CC1005-0402")
      (description "Capacitor (Semiconductor SIM Model)")
      (fields (field (name "PUBLISHER") "Altium Limited"))
      (libsource (lib "Miscellaneous Devices") (part "Cap Semi"))
    )
    (comp (ref "C191")
      (value "47nF")
      (footprint "CC1005-0402")
      (description "Capacitor (Semiconductor SIM Model)")
      (fields (field (name "PUBLISHER") "Altium Limited"))
      (libsource (lib "Miscellaneous Devices") (part "Cap Semi"))
    )
    (comp (ref "C192")
      (value "47nF")
      (footprint "CC1005-0402")
      (description "Capacitor (Semiconductor SIM Model)")
      (fields (field (name "PUBLISHER") "Altium Limited"))
      (libsource (lib "Miscellaneous Devices") (part "Cap Semi"))
    )
    (comp (ref "C193")
      (value "47nF")
      (footprint "CC1005-0402")
      (description "Capacitor (Semiconductor SIM Model)")
      (fields (field (name "PUBLISHER") "Altium Limited"))
      (libsource (lib "Miscellaneous Devices") (part "Cap Semi"))
    )
    (comp (ref "C194")
      (value "47nF")
      (footprint "CC1005-0402")
      (description "Capacitor (Semiconductor SIM Model)")
      (fields (field (name "PUBLISHER") "Altium Limited"))
      (libsource (lib "Miscellaneous Devices") (part "Cap Semi"))
    )
    (comp (ref "C195")
      (value "47nF")
      (footprint "CC1005-0402")
      (description "Capacitor (Semiconductor SIM Model)")
      (fields (field (name "PUBLISHER") "Altium Limited"))
      (libsource (lib "Miscellaneous Devices") (part "Cap Semi"))
    )
    (comp (ref "C196")
      (value "47nF")
      (footprint "CC1005-0402")
      (description "Capacitor (Semiconductor SIM Model)")
      (fields (field (name "PUBLISHER") "Altium Limited"))
      (libsource (lib "Miscellaneous Devices") (part "Cap Semi"))
    )
    (comp (ref "C197")
      (value "47nF")
      (footprint "CC1005-0402")
      (description "Capacitor (Semiconductor SIM Model)")
      (fields (field (name "PUBLISHER") "Altium Limited"))
      (libsource (lib "Miscellaneous Devices") (part "Cap Semi"))
    )
    (comp (ref "C198")
      (value "47nF")
      (footprint "CC1005-0402")
      (description "Capacitor (Semiconductor SIM Model)")
      (fields (field (name "PUBLISHER") "Altium Limited"))
      (libsource (lib "Miscellaneous Devices") (part "Cap Semi"))
    )
    (comp (ref "C199")
      (value "47nF")
      (footprint "CC1005-0402")
      (description "Capacitor (Semiconductor SIM Model)")
      (fields (field (name "PUBLISHER") "Altium Limited"))
      (libsource (lib "Miscellaneous Devices") (part "Cap Semi"))
    )
    (comp (ref "C200")
      (value "47nF")
      (footprint "CC1005-0402")
      (description "Capacitor (Semiconductor SIM Model)")
      (fields (field (name "PUBLISHER") "Altium Limited"))
      (libsource (lib "Miscellaneous Devices") (part "Cap Semi"))
    )
    (comp (ref "C201")
      (value "47nF")
      (footprint "CC1005-0402")
      (description "Capacitor (Semiconductor SIM Model)")
      (fields (field (name "PUBLISHER") "Altium Limited"))
      (libsource (lib "Miscellaneous Devices") (part "Cap Semi"))
    )
    (comp (ref "C202")
      (value "47nF")
      (footprint "CC1005-0402")
      (description "Capacitor (Semiconductor SIM Model)")
      (fields (field (name "PUBLISHER") "Altium Limited"))
      (libsource (lib "Miscellaneous Devices") (part "Cap Semi"))
    )
    (comp (ref "C203")
      (value "47nF")
      (footprint "CC1005-0402")
      (description "Capacitor (Semiconductor SIM Model)")
      (fields (field (name "PUBLISHER") "Altium Limited"))
      (libsource (lib "Miscellaneous Devices") (part "Cap Semi"))
    )
    (comp (ref "C204")
      (value "0.22uF")
      (footprint "CC1608-0603")
      (description "Capacitor (Semiconductor SIM Model)")
      (fields (field (name "PUBLISHER") "Altium Limited"))
      (libsource (lib "Miscellaneous Devices") (part "Cap Semi"))
    )
    (comp (ref "C205")
      (value "0.22uF")
      (footprint "CC1608-0603")
      (description "Capacitor (Semiconductor SIM Model)")
      (fields (field (name "PUBLISHER") "Altium Limited"))
      (libsource (lib "Miscellaneous Devices") (part "Cap Semi"))
    )
    (comp (ref "C206")
      (value "0.22uF")
      (footprint "CC1608-0603")
      (description "Capacitor (Semiconductor SIM Model)")
      (fields (field (name "PUBLISHER") "Altium Limited"))
      (libsource (lib "Miscellaneous Devices") (part "Cap Semi"))
    )
    (comp (ref "C207")
      (value "0.22uF")
      (footprint "CC1608-0603")
      (description "Capacitor (Semiconductor SIM Model)")
      (fields (field (name "PUBLISHER") "Altium Limited"))
      (libsource (lib "Miscellaneous Devices") (part "Cap Semi"))
    )
    (comp (ref "C208")
      (value "0.22uF")
      (footprint "CC1608-0603")
      (description "Capacitor (Semiconductor SIM Model)")
      (fields (field (name "PUBLISHER") "Altium Limited"))
      (libsource (lib "Miscellaneous Devices") (part "Cap Semi"))
    )
    (comp (ref "C209")
      (value "0.22uF")
      (footprint "CC1608-0603")
      (description "Capacitor (Semiconductor SIM Model)")
      (fields (field (name "PUBLISHER") "Altium Limited"))
      (libsource (lib "Miscellaneous Devices") (part "Cap Semi"))
    )
    (comp (ref "C210")
      (value "0.22uF")
      (footprint "CC1608-0603")
      (description "Capacitor (Semiconductor SIM Model)")
      (fields (field (name "PUBLISHER") "Altium Limited"))
      (libsource (lib "Miscellaneous Devices") (part "Cap Semi"))
    )
    (comp (ref "C211")
      (value "0.22uF")
      (footprint "CC1608-0603")
      (description "Capacitor (Semiconductor SIM Model)")
      (fields (field (name "PUBLISHER") "Altium Limited"))
      (libsource (lib "Miscellaneous Devices") (part "Cap Semi"))
    )
    (comp (ref "C212")
      (value "0.22uF")
      (footprint "CC1608-0603")
      (description "Capacitor (Semiconductor SIM Model)")
      (fields (field (name "PUBLISHER") "Altium Limited"))
      (libsource (lib "Miscellaneous Devices") (part "Cap Semi"))
    )
    (comp (ref "C213")
      (value "0.22uF")
      (footprint "CC1608-0603")
      (description "Capacitor (Semiconductor SIM Model)")
      (fields (field (name "PUBLISHER") "Altium Limited"))
      (libsource (lib "Miscellaneous Devices") (part "Cap Semi"))
    )
    (comp (ref "C214")
      (value "0.22uF")
      (footprint "CC1608-0603")
      (description "Capacitor (Semiconductor SIM Model)")
      (fields (field (name "PUBLISHER") "Altium Limited"))
      (libsource (lib "Miscellaneous Devices") (part "Cap Semi"))
    )
    (comp (ref "C215")
      (value "0.22uF")
      (footprint "CC1608-0603")
      (description "Capacitor (Semiconductor SIM Model)")
      (fields (field (name "PUBLISHER") "Altium Limited"))
      (libsource (lib "Miscellaneous Devices") (part "Cap Semi"))
    )
    (comp (ref "C216")
      (value "0.22uF")
      (footprint "CC1608-0603")
      (description "Capacitor (Semiconductor SIM Model)")
      (fields (field (name "PUBLISHER") "Altium Limited"))
      (libsource (lib "Miscellaneous Devices") (part "Cap Semi"))
    )
    (comp (ref "C217")
      (value "0.22uF")
      (footprint "CC1608-0603")
      (description "Capacitor (Semiconductor SIM Model)")
      (fields (field (name "PUBLISHER") "Altium Limited"))
      (libsource (lib "Miscellaneous Devices") (part "Cap Semi"))
    )
    (comp (ref "C218")
      (value "0.22uF")
      (footprint "CC1608-0603")
      (description "Capacitor (Semiconductor SIM Model)")
      (fields (field (name "PUBLISHER") "Altium Limited"))
      (libsource (lib "Miscellaneous Devices") (part "Cap Semi"))
    )
    (comp (ref "C219")
      (value "0.22uF")
      (footprint "CC1608-0603")
      (description "Capacitor (Semiconductor SIM Model)")
      (fields (field (name "PUBLISHER") "Altium Limited"))
      (libsource (lib "Miscellaneous Devices") (part "Cap Semi"))
    )
    (comp (ref "C220")
      (value "0.22uF")
      (footprint "CC1608-0603")
      (description "Capacitor (Semiconductor SIM Model)")
      (fields (field (name "PUBLISHER") "Altium Limited"))
      (libsource (lib "Miscellaneous Devices") (part "Cap Semi"))
    )
    (comp (ref "C221")
      (value "0.68uF")
      (footprint "CC3216-1206")
      (description "Capacitor (Semiconductor SIM Model)")
      (fields (field (name "PUBLISHER") "Altium Limited"))
      (libsource (lib "Miscellaneous Devices") (part "Cap Semi"))
    )
    (comp (ref "C222")
      (value "0.68uF")
      (footprint "CC3216-1206")
      (description "Capacitor (Semiconductor SIM Model)")
      (fields (field (name "PUBLISHER") "Altium Limited"))
      (libsource (lib "Miscellaneous Devices") (part "Cap Semi"))
    )
    (comp (ref "C223")
      (value "0.68uF")
      (footprint "CC3216-1206")
      (description "Capacitor (Semiconductor SIM Model)")
      (fields (field (name "PUBLISHER") "Altium Limited"))
      (libsource (lib "Miscellaneous Devices") (part "Cap Semi"))
    )
    (comp (ref "C224")
      (value "0.68uF")
      (footprint "CC3216-1206")
      (description "Capacitor (Semiconductor SIM Model)")
      (fields (field (name "PUBLISHER") "Altium Limited"))
      (libsource (lib "Miscellaneous Devices") (part "Cap Semi"))
    )
    (comp (ref "C225")
      (value "0.68uF")
      (footprint "CC3216-1206")
      (description "Capacitor (Semiconductor SIM Model)")
      (fields (field (name "PUBLISHER") "Altium Limited"))
      (libsource (lib "Miscellaneous Devices") (part "Cap Semi"))
    )
    (comp (ref "C226")
      (value "0.68uF")
      (footprint "CC3216-1206")
      (description "Capacitor (Semiconductor SIM Model)")
      (fields (field (name "PUBLISHER") "Altium Limited"))
      (libsource (lib "Miscellaneous Devices") (part "Cap Semi"))
    )
    (comp (ref "C227")
      (value "0.68uF")
      (footprint "CC3216-1206")
      (description "Capacitor (Semiconductor SIM Model)")
      (fields (field (name "PUBLISHER") "Altium Limited"))
      (libsource (lib "Miscellaneous Devices") (part "Cap Semi"))
    )
    (comp (ref "C228")
      (value "0.68uF")
      (footprint "CC3216-1206")
      (description "Capacitor (Semiconductor SIM Model)")
      (fields (field (name "PUBLISHER") "Altium Limited"))
      (libsource (lib "Miscellaneous Devices") (part "Cap Semi"))
    )
    (comp (ref "C229")
      (value "2.2uF")
      (footprint "CC3216-1206")
      (description "Capacitor (Semiconductor SIM Model)")
      (fields (field (name "PUBLISHER") "Altium Limited"))
      (libsource (lib "Miscellaneous Devices") (part "Cap Semi"))
    )
    (comp (ref "C230")
      (value "2.2uF")
      (footprint "CC3216-1206")
      (description "Capacitor (Semiconductor SIM Model)")
      (fields (field (name "PUBLISHER") "Altium Limited"))
      (libsource (lib "Miscellaneous Devices") (part "Cap Semi"))
    )
    (comp (ref "C231")
      (value "2.2uF")
      (footprint "CC3216-1206")
      (description "Capacitor (Semiconductor SIM Model)")
      (fields (field (name "PUBLISHER") "Altium Limited"))
      (libsource (lib "Miscellaneous Devices") (part "Cap Semi"))
    )
    (comp (ref "C232")
      (value "2.2uF")
      (footprint "CC3216-1206")
      (description "Capacitor (Semiconductor SIM Model)")
      (fields (field (name "PUBLISHER") "Altium Limited"))
      (libsource (lib "Miscellaneous Devices") (part "Cap Semi"))
    )
    (comp (ref "C233")
      (value "2.2uF")
      (footprint "CC3216-1206")
      (description "Capacitor (Semiconductor SIM Model)")
      (fields (field (name "PUBLISHER") "Altium Limited"))
      (libsource (lib "Miscellaneous Devices") (part "Cap Semi"))
    )
    (comp (ref "C234")
      (value "2.2uF")
      (footprint "CC3216-1206")
      (description "Capacitor (Semiconductor SIM Model)")
      (fields (field (name "PUBLISHER") "Altium Limited"))
      (libsource (lib "Miscellaneous Devices") (part "Cap Semi"))
    )
    (comp (ref "C235")
      (value "330uF x 10V")
      (footprint "CC7343-31_Dsize")
      (description "CAP TANTD TPSD337K010R0100")
      (fields (field (name "PUBLISHER") "Altium Limited"))
      (libsource (lib "Miscellaneous Devices") (part "Cap Pol3"))
    )
    (comp (ref "U1")
      (value "XC4VLX100-11FF1148C")
      (footprint "FF1148")
      (description "Xilinx Virtex-4 LX Platform FPGA, 1148-Ball FFBGA, Speed Grade 11, 768 User I/Os, Commercial Grade")
      (fields (field (name "PUBLISHER") "Altium Limited"))
      (libsource (lib "Xilinx Virtex-4") (part "XC4VLX100-11FF1148C"))
    )
  )
  (nets
    (net (code "1") (name "GND") (class "Default")
      (node (ref "C100") (pin "1") (pinfunction "1_1") (pintype "passive"))
      (node (ref "C101") (pin "1") (pinfunction "1_1") (pintype "passive"))
      (node (ref "C102") (pin "1") (pinfunction "1_1") (pintype "passive"))
      (node (ref "C103") (pin "1") (pinfunction "1_1") (pintype "passive"))
      (node (ref "C104") (pin "1") (pinfunction "1_1") (pintype "passive"))
      (node (ref "C105") (pin "1") (pinfunction "1_1") (pintype "passive"))
      (node (ref "C106") (pin "1") (pinfunction "1_1") (pintype "passive"))
      (node (ref "C107") (pin "1") (pinfunction "1_1") (pintype "passive"))
      (node (ref "C108") (pin "1") (pinfunction "1_1") (pintype "passive"))
      (node (ref "C109") (pin "1") (pinfunction "1_1") (pintype "passive"))
      (node (ref "C110") (pin "1") (pinfunction "1_1") (pintype "passive"))
      (node (ref "C111") (pin "1") (pinfunction "1_1") (pintype "passive"))
      (node (ref "C112") (pin "2") (pinfunction "2_2") (pintype "passive"))
      (node (ref "C113") (pin "2") (pinfunction "2_2") (pintype "passive"))
      (node (ref "C114") (pin "2") (pinfunction "2_2") (pintype "passive"))
      (node (ref "C115") (pin "2") (pinfunction "2_2") (pintype "passive"))
      (node (ref "C116") (pin "2") (pinfunction "2_2") (pintype "passive"))
      (node (ref "C117") (pin "2") (pinfunction "2_2") (pintype "passive"))
      (node (ref "C118") (pin "2") (pinfunction "2_2") (pintype "passive"))
      (node (ref "C119") (pin "2") (pinfunction "2_2") (pintype "passive"))
      (node (ref "C120") (pin "2") (pinfunction "2_2") (pintype "passive"))
      (node (ref "C121") (pin "1") (pinfunction "1_1") (pintype "passive"))
      (node (ref "C122") (pin "1") (pinfunction "1_1") (pintype "passive"))
      (node (ref "C123") (pin "1") (pinfunction "1_1") (pintype "passive"))
      (node (ref "C124") (pin "1") (pinfunction "1_1") (pintype "passive"))
      (node (ref "C125") (pin "1") (pinfunction "1_1") (pintype "passive"))
      (node (ref "C126") (pin "1") (pinfunction "1_1") (pintype "passive"))
      (node (ref "C127") (pin "1") (pinfunction "1_1") (pintype "passive"))
      (node (ref "C128") (pin "1") (pinfunction "1_1") (pintype "passive"))
      (node (ref "C129") (pin "1") (pinfunction "1_1") (pintype "passive"))
      (node (ref "C130") (pin "1") (pinfunction "1_1") (pintype "passive"))
      (node (ref "C131") (pin "1") (pinfunction "1_1") (pintype "passive"))
      (node (ref "C132") (pin "1") (pinfunction "1_1") (pintype "passive"))
      (node (ref "C133") (pin "1") (pinfunction "1_1") (pintype "passive"))
      (node (ref "C134") (pin "1") (pinfunction "1_1") (pintype "passive"))
      (node (ref "C135") (pin "1") (pinfunction "1_1") (pintype "passive"))
      (node (ref "C136") (pin "1") (pinfunction "1_1") (pintype "passive"))
      (node (ref "C137") (pin "1") (pinfunction "1_1") (pintype "passive"))
      (node (ref "C138") (pin "1") (pinfunction "1_1") (pintype "passive"))
      (node (ref "C139") (pin "1") (pinfunction "1_1") (pintype "passive"))
      (node (ref "C140") (pin "1") (pinfunction "1_1") (pintype "passive"))
      (node (ref "C141") (pin "1") (pinfunction "1_1") (pintype "passive"))
      (node (ref "C142") (pin "1") (pinfunction "1_1") (pintype "passive"))
      (node (ref "C143") (pin "1") (pinfunction "1_1") (pintype "passive"))
      (node (ref "C144") (pin "1") (pinfunction "1_1") (pintype "passive"))
      (node (ref "C145") (pin "1") (pinfunction "1_1") (pintype "passive"))
      (node (ref "C146") (pin "1") (pinfunction "1_1") (pintype "passive"))
      (node (ref "C147") (pin "1") (pinfunction "1_1") (pintype "passive"))
      (node (ref "C148") (pin "2") (pinfunction "2_2") (pintype "passive"))
      (node (ref "C149") (pin "1") (pinfunction "1_1") (pintype "passive"))
      (node (ref "C150") (pin "1") (pinfunction "1_1") (pintype "passive"))
      (node (ref "C151") (pin "1") (pinfunction "1_1") (pintype "passive"))
      (node (ref "C152") (pin "1") (pinfunction "1_1") (pintype "passive"))
      (node (ref "C153") (pin "1") (pinfunction "1_1") (pintype "passive"))
      (node (ref "C154") (pin "1") (pinfunction "1_1") (pintype "passive"))
      (node (ref "C155") (pin "1") (pinfunction "1_1") (pintype "passive"))
      (node (ref "C156") (pin "1") (pinfunction "1_1") (pintype "passive"))
      (node (ref "C157") (pin "1") (pinfunction "1_1") (pintype "passive"))
      (node (ref "C158") (pin "2") (pinfunction "2_2") (pintype "passive"))
      (node (ref "C159") (pin "2") (pinfunction "2_2") (pintype "passive"))
      (node (ref "C160") (pin "2") (pinfunction "2_2") (pintype "passive"))
      (node (ref "C161") (pin "2") (pinfunction "2_2") (pintype "passive"))
      (node (ref "C162") (pin "2") (pinfunction "2_2") (pintype "passive"))
      (node (ref "C163") (pin "2") (pinfunction "2_2") (pintype "passive"))
      (node (ref "C164") (pin "2") (pinfunction "2_2") (pintype "passive"))
      (node (ref "C165") (pin "2") (pinfunction "2_2") (pintype "passive"))
      (node (ref "C166") (pin "2") (pinfunction "2_2") (pintype "passive"))
      (node (ref "C167") (pin "2") (pinfunction "2_2") (pintype "passive"))
      (node (ref "C168") (pin "2") (pinfunction "2_2") (pintype "passive"))
      (node (ref "C169") (pin "1") (pinfunction "1_1") (pintype "passive"))
      (node (ref "C170") (pin "1") (pinfunction "1_1") (pintype "passive"))
      (node (ref "C171") (pin "2") (pinfunction "2_2") (pintype "passive"))
      (node (ref "C172") (pin "1") (pinfunction "1_1") (pintype "passive"))
      (node (ref "C173") (pin "1") (pinfunction "1_1") (pintype "passive"))
      (node (ref "C174") (pin "1") (pinfunction "1_1") (pintype "passive"))
      (node (ref "C175") (pin "2") (pinfunction "2_2") (pintype "passive"))
      (node (ref "C176") (pin "1") (pinfunction "1_1") (pintype "passive"))
      (node (ref "C177") (pin "1") (pinfunction "1_1") (pintype "passive"))
      (node (ref "C178") (pin "2") (pinfunction "2_2") (pintype "passive"))
      (node (ref "C179") (pin "2") (pinfunction "2_2") (pintype "passive"))
      (node (ref "C180") (pin "2") (pinfunction "2_2") (pintype "passive"))
      (node (ref "C181") (pin "2") (pinfunction "2_2") (pintype "passive"))
      (node (ref "C182") (pin "2") (pinfunction "2_2") (pintype "passive"))
      (node (ref "C183") (pin "2") (pinfunction "2_2") (pintype "passive"))
      (node (ref "C184") (pin "2") (pinfunction "2_2") (pintype "passive"))
      (node (ref "C185") (pin "1") (pinfunction "1_1") (pintype "passive"))
      (node (ref "C186") (pin "1") (pinfunction "1_1") (pintype "passive"))
      (node (ref "C187") (pin "1") (pinfunction "1_1") (pintype "passive"))
      (node (ref "C188") (pin "1") (pinfunction "1_1") (pintype "passive"))
      (node (ref "C189") (pin "1") (pinfunction "1_1") (pintype "passive"))
      (node (ref "C190") (pin "1") (pinfunction "1_1") (pintype "passive"))
      (node (ref "C191") (pin "1") (pinfunction "1_1") (pintype "passive"))
      (node (ref "C192") (pin "1") (pinfunction "1_1") (pintype "passive"))
      (node (ref "C193") (pin "1") (pinfunction "1_1") (pintype "passive"))
      (node (ref "C194") (pin "1") (pinfunction "1_1") (pintype "passive"))
      (node (ref "C195") (pin "1") (pinfunction "1_1") (pintype "passive"))
      (node (ref "C196") (pin "1") (pinfunction "1_1") (pintype "passive"))
      (node (ref "C197") (pin "1") (pinfunction "1_1") (pintype "passive"))
      (node (ref "C198") (pin "1") (pinfunction "1_1") (pintype "passive"))
      (node (ref "C199") (pin "1") (pinfunction "1_1") (pintype "passive"))
      (node (ref "C200") (pin "1") (pinfunction "1_1") (pintype "passive"))
      (node (ref "C201") (pin "1") (pinfunction "1_1") (pintype "passive"))
      (node (ref "C202") (pin "1") (pinfunction "1_1") (pintype "passive"))
      (node (ref "C203") (pin "1") (pinfunction "1_1") (pintype "passive"))
      (node (ref "C204") (pin "1") (pinfunction "1_1") (pintype "passive"))
      (node (ref "C205") (pin "1") (pinfunction "1_1") (pintype "passive"))
      (node (ref "C206") (pin "1") (pinfunction "1_1") (pintype "passive"))
      (node (ref "C207") (pin "1") (pinfunction "1_1") (pintype "passive"))
      (node (ref "C208") (pin "1") (pinfunction "1_1") (pintype "passive"))
      (node (ref "C209") (pin "1") (pinfunction "1_1") (pintype "passive"))
      (node (ref "C210") (pin "1") (pinfunction "1_1") (pintype "passive"))
      (node (ref "C211") (pin "1") (pinfunction "1_1") (pintype "passive"))
      (node (ref "C212") (pin "1") (pinfunction "1_1") (pintype "passive"))
      (node (ref "C213") (pin "1") (pinfunction "1_1") (pintype "passive"))
      (node (ref "C214") (pin "1") (pinfunction "1_1") (pintype "passive"))
      (node (ref "C215") (pin "1") (pinfunction "1_1") (pintype "passive"))
      (node (ref "C216") (pin "1") (pinfunction "1_1") (pintype "passive"))
      (node (ref "C217") (pin "1") (pinfunction "1_1") (pintype "passive"))
      (node (ref "C218") (pin "1") (pinfunction "1_1") (pintype "passive"))
      (node (ref "C219") (pin "1") (pinfunction "1_1") (pintype "passive"))
      (node (ref "C220") (pin "1") (pinfunction "1_1") (pintype "passive"))
      (node (ref "C221") (pin "1") (pinfunction "1_1") (pintype "passive"))
      (node (ref "C222") (pin "1") (pinfunction "1_1") (pintype "passive"))
      (node (ref "C223") (pin "1") (pinfunction "1_1") (pintype "passive"))
      (node (ref "C224") (pin "1") (pinfunction "1_1") (pintype "passive"))
      (node (ref "C225") (pin "1") (pinfunction "1_1") (pintype "passive"))
      (node (ref "C226") (pin "1") (pinfunction "1_1") (pintype "passive"))
      (node (ref "C227") (pin "1") (pinfunction "1_1") (pintype "passive"))
      (node (ref "C228") (pin "1") (pinfunction "1_1") (pintype "passive"))
      (node (ref "C229") (pin "1") (pinfunction "1_1") (pintype "passive"))
      (node (ref "C230") (pin "1") (pinfunction "1_1") (pintype "passive"))
      (node (ref "C231") (pin "1") (pinfunction "1_1") (pintype "passive"))
      (node (ref "C232") (pin "1") (pinfunction "1_1") (pintype "passive"))
      (node (ref "C233") (pin "1") (pinfunction "1_1") (pintype "passive"))
      (node (ref "C234") (pin "1") (pinfunction "1_1") (pintype "passive"))
      (node (ref "C235") (pin "2") (pinfunction "2_2") (pintype "passive"))
      (node (ref "C46") (pin "2") (pinfunction "2_2") (pintype "passive"))
      (node (ref "C47") (pin "2") (pinfunction "2_2") (pintype "passive"))
      (node (ref "C48") (pin "2") (pinfunction "2_2") (pintype "passive"))
      (node (ref "C49") (pin "2") (pinfunction "2_2") (pintype "passive"))
      (node (ref "C50") (pin "2") (pinfunction "2_2") (pintype "passive"))
      (node (ref "C51") (pin "2") (pinfunction "2_2") (pintype "passive"))
      (node (ref "C52") (pin "2") (pinfunction "2_2") (pintype "passive"))
      (node (ref "C53") (pin "2") (pinfunction "2_2") (pintype "passive"))
      (node (ref "C54") (pin "2") (pinfunction "2_2") (pintype "passive"))
      (node (ref "C55") (pin "2") (pinfunction "2_2") (pintype "passive"))
      (node (ref "C56") (pin "2") (pinfunction "2_2") (pintype "passive"))
      (node (ref "C57") (pin "2") (pinfunction "2_2") (pintype "passive"))
      (node (ref "C58") (pin "2") (pinfunction "2_2") (pintype "passive"))
      (node (ref "C59") (pin "2") (pinfunction "2_2") (pintype "passive"))
      (node (ref "C60") (pin "2") (pinfunction "2_2") (pintype "passive"))
      (node (ref "C61") (pin "2") (pinfunction "2_2") (pintype "passive"))
      (node (ref "C62") (pin "2") (pinfunction "2_2") (pintype "passive"))
      (node (ref "C63") (pin "2") (pinfunction "2_2") (pintype "passive"))
      (node (ref "C64") (pin "2") (pinfunction "2_2") (pintype "passive"))
      (node (ref "C65") (pin "2") (pinfunction "2_2") (pintype "passive"))
      (node (ref "C66") (pin "2") (pinfunction "2_2") (pintype "passive"))
      (node (ref "C67") (pin "1") (pinfunction "1_1") (pintype "passive"))
      (node (ref "C68") (pin "1") (pinfunction "1_1") (pintype "passive"))
      (node (ref "C69") (pin "1") (pinfunction "1_1") (pintype "passive"))
      (node (ref "C70") (pin "1") (pinfunction "1_1") (pintype "passive"))
      (node (ref "C71") (pin "1") (pinfunction "1_1") (pintype "passive"))
      (node (ref "C72") (pin "1") (pinfunction "1_1") (pintype "passive"))
      (node (ref "C73") (pin "1") (pinfunction "1_1") (pintype "passive"))
      (node (ref "C74") (pin "1") (pinfunction "1_1") (pintype "passive"))
      (node (ref "C75") (pin "1") (pinfunction "1_1") (pintype "passive"))
      (node (ref "C76") (pin "1") (pinfunction "1_1") (pintype "passive"))
      (node (ref "C77") (pin "1") (pinfunction "1_1") (pintype "passive"))
      (node (ref "C78") (pin "1") (pinfunction "1_1") (pintype "passive"))
      (node (ref "C79") (pin "1") (pinfunction "1_1") (pintype "passive"))
      (node (ref "C80") (pin "1") (pinfunction "1_1") (pintype "passive"))
      (node (ref "C81") (pin "1") (pinfunction "1_1") (pintype "passive"))
      (node (ref "C82") (pin "1") (pinfunction "1_1") (pintype "passive"))
      (node (ref "C83") (pin "1") (pinfunction "1_1") (pintype "passive"))
      (node (ref "C84") (pin "1") (pinfunction "1_1") (pintype "passive"))
      (node (ref "C85") (pin "1") (pinfunction "1_1") (pintype "passive"))
      (node (ref "C86") (pin "1") (pinfunction "1_1") (pintype "passive"))
      (node (ref "C87") (pin "1") (pinfunction "1_1") (pintype "passive"))
      (node (ref "C88") (pin "1") (pinfunction "1_1") (pintype "passive"))
      (node (ref "C89") (pin "1") (pinfunction "1_1") (pintype "passive"))
      (node (ref "C90") (pin "1") (pinfunction "1_1") (pintype "passive"))
      (node (ref "C91") (pin "1") (pinfunction "1_1") (pintype "passive"))
      (node (ref "C92") (pin "1") (pinfunction "1_1") (pintype "passive"))
      (node (ref "C93") (pin "1") (pinfunction "1_1") (pintype "passive"))
      (node (ref "C94") (pin "1") (pinfunction "1_1") (pintype "passive"))
      (node (ref "C95") (pin "1") (pinfunction "1_1") (pintype "passive"))
      (node (ref "C96") (pin "1") (pinfunction "1_1") (pintype "passive"))
      (node (ref "C97") (pin "1") (pinfunction "1_1") (pintype "passive"))
      (node (ref "C98") (pin "1") (pinfunction "1_1") (pintype "passive"))
      (node (ref "C99") (pin "1") (pinfunction "1_1") (pintype "passive"))
      (node (ref "U1") (pin "A16") (pinfunction "AVSS_ADC_A16") (pintype "input"))
      (node (ref "U1") (pin "A17") (pinfunction "VN_ADC_A17") (pintype "input"))
      (node (ref "U1") (pin "A18") (pinfunction "VP_ADC_A18") (pintype "input"))
      (node (ref "U1") (pin "A19") (pinfunction "GND_A19") (pintype "power_in"))
      (node (ref "U1") (pin "A27") (pinfunction "GND_A27") (pintype "power_in"))
      (node (ref "U1") (pin "A33") (pinfunction "GND_A33") (pintype "power_in"))
      (node (ref "U1") (pin "A7") (pinfunction "GND_A7") (pintype "power_in"))
      (node (ref "U1") (pin "AA17") (pinfunction "GND_AA17") (pintype "power_in"))
      (node (ref "U1") (pin "AA19") (pinfunction "GND_AA19") (pintype "power_in"))
      (node (ref "U1") (pin "AA27") (pinfunction "GND_AA27") (pintype "power_in"))
      (node (ref "U1") (pin "AA7") (pinfunction "GND_AA7") (pintype "power_in"))
      (node (ref "U1") (pin "AB14") (pinfunction "GND_AB14") (pintype "power_in"))
      (node (ref "U1") (pin "AB20") (pinfunction "GND_AB20") (pintype "power_in"))
      (node (ref "U1") (pin "AB24") (pinfunction "GND_AB24") (pintype "power_in"))
      (node (ref "U1") (pin "AB34") (pinfunction "GND_AB34") (pintype "power_in"))
      (node (ref "U1") (pin "AB4") (pinfunction "GND_AB4") (pintype "power_in"))
      (node (ref "U1") (pin "AC1") (pinfunction "GND_AC1") (pintype "power_in"))
      (node (ref "U1") (pin "AC11") (pinfunction "GND_AC11") (pintype "power_in"))
      (node (ref "U1") (pin "AC13") (pinfunction "GND_AC13") (pintype "power_in"))
      (node (ref "U1") (pin "AC21") (pinfunction "GND_AC21") (pintype "power_in"))
      (node (ref "U1") (pin "AC23") (pinfunction "GND_AC23") (pintype "power_in"))
      (node (ref "U1") (pin "AC31") (pinfunction "GND_AC31") (pintype "power_in"))
      (node (ref "U1") (pin "AD12") (pinfunction "GND_AD12") (pintype "power_in"))
      (node (ref "U1") (pin "AD14") (pinfunction "GND_AD14") (pintype "power_in"))
      (node (ref "U1") (pin "AD18") (pinfunction "GND_AD18") (pintype "power_in"))
      (node (ref "U1") (pin "AD22") (pinfunction "GND_AD22") (pintype "power_in"))
      (node (ref "U1") (pin "AD24") (pinfunction "GND_AD24") (pintype "power_in"))
      (node (ref "U1") (pin "AD28") (pinfunction "GND_AD28") (pintype "power_in"))
      (node (ref "U1") (pin "AD8") (pinfunction "GND_AD8") (pintype "power_in"))
      (node (ref "U1") (pin "AE13") (pinfunction "GND_AE13") (pintype "power_in"))
      (node (ref "U1") (pin "AE15") (pinfunction "GND_AE15") (pintype "power_in"))
      (node (ref "U1") (pin "AE23") (pinfunction "GND_AE23") (pintype "power_in"))
      (node (ref "U1") (pin "AE25") (pinfunction "GND_AE25") (pintype "power_in"))
      (node (ref "U1") (pin "AE5") (pinfunction "GND_AE5") (pintype "power_in"))
      (node (ref "U1") (pin "AF12") (pinfunction "GND_AF12") (pintype "power_in"))
      (node (ref "U1") (pin "AF2") (pinfunction "GND_AF2") (pintype "power_in"))
      (node (ref "U1") (pin "AF22") (pinfunction "GND_AF22") (pintype "power_in"))
      (node (ref "U1") (pin "AF32") (pinfunction "GND_AF32") (pintype "power_in"))
      (node (ref "U1") (pin "AG19") (pinfunction "GND_AG19") (pintype "power_in"))
      (node (ref "U1") (pin "AG29") (pinfunction "GND_AG29") (pintype "power_in"))
      (node (ref "U1") (pin "AG9") (pinfunction "GND_AG9") (pintype "power_in"))
      (node (ref "U1") (pin "AH16") (pinfunction "GND_AH16") (pintype "power_in"))
      (node (ref "U1") (pin "AH26") (pinfunction "GND_AH26") (pintype "power_in"))
      (node (ref "U1") (pin "AH6") (pinfunction "GND_AH6") (pintype "power_in"))
      (node (ref "U1") (pin "AJ13") (pinfunction "GND_AJ13") (pintype "power_in"))
      (node (ref "U1") (pin "AJ23") (pinfunction "GND_AJ23") (pintype "power_in"))
      (node (ref "U1") (pin "AJ3") (pinfunction "GND_AJ3") (pintype "power_in"))
      (node (ref "U1") (pin "AJ33") (pinfunction "GND_AJ33") (pintype "power_in"))
      (node (ref "U1") (pin "AK10") (pinfunction "GND_AK10") (pintype "power_in"))
      (node (ref "U1") (pin "AK20") (pinfunction "GND_AK20") (pintype "power_in"))
      (node (ref "U1") (pin "AK30") (pinfunction "GND_AK30") (pintype "power_in"))
      (node (ref "U1") (pin "AL17") (pinfunction "GND_AL17") (pintype "power_in"))
      (node (ref "U1") (pin "AL27") (pinfunction "GND_AL27") (pintype "power_in"))
      (node (ref "U1") (pin "AL7") (pinfunction "GND_AL7") (pintype "power_in"))
      (node (ref "U1") (pin "AM14") (pinfunction "GND_AM14") (pintype "power_in"))
      (node (ref "U1") (pin "AM24") (pinfunction "GND_AM24") (pintype "power_in"))
      (node (ref "U1") (pin "AM34") (pinfunction "GND_AM34") (pintype "power_in"))
      (node (ref "U1") (pin "AM4") (pinfunction "GND_AM4") (pintype "power_in"))
      (node (ref "U1") (pin "AN1") (pinfunction "GND_AN1") (pintype "power_in"))
      (node (ref "U1") (pin "AN11") (pinfunction "GND_AN11") (pintype "power_in"))
      (node (ref "U1") (pin "AN17") (pinfunction "VREFN_SM_AN17") (pintype "input"))
      (node (ref "U1") (pin "AN18") (pinfunction "VREFP_SM_AN18") (pintype "input"))
      (node (ref "U1") (pin "AN19") (pinfunction "AVSS_SM_AN19") (pintype "input"))
      (node (ref "U1") (pin "AN21") (pinfunction "GND_AN21") (pintype "power_in"))
      (node (ref "U1") (pin "AN31") (pinfunction "GND_AN31") (pintype "power_in"))
      (node (ref "U1") (pin "AN34") (pinfunction "GND_AN34") (pintype "power_in"))
      (node (ref "U1") (pin "AP16") (pinfunction "GND_AP16") (pintype "power_in"))
      (node (ref "U1") (pin "AP17") (pinfunction "VN_SM_AP17") (pintype "input"))
      (node (ref "U1") (pin "AP18") (pinfunction "VP_SM_AP18") (pintype "input"))
      (node (ref "U1") (pin "AP2") (pinfunction "GND_AP2") (pintype "power_in"))
      (node (ref "U1") (pin "AP28") (pinfunction "GND_AP28") (pintype "power_in"))
      (node (ref "U1") (pin "AP8") (pinfunction "GND_AP8") (pintype "power_in"))
      (node (ref "U1") (pin "B1") (pinfunction "GND_B1") (pintype "power_in"))
      (node (ref "U1") (pin "B14") (pinfunction "GND_B14") (pintype "power_in"))
      (node (ref "U1") (pin "B17") (pinfunction "VREFN_ADC_B17") (pintype "input"))
      (node (ref "U1") (pin "B18") (pinfunction "VREFP_ADC_B18") (pintype "input"))
      (node (ref "U1") (pin "B24") (pinfunction "GND_B24") (pintype "power_in"))
      (node (ref "U1") (pin "B34") (pinfunction "GND_B34") (pintype "power_in"))
      (node (ref "U1") (pin "B4") (pinfunction "GND_B4") (pintype "power_in"))
      (node (ref "U1") (pin "C1") (pinfunction "GND_C1") (pintype "power_in"))
      (node (ref "U1") (pin "C11") (pinfunction "GND_C11") (pintype "power_in"))
      (node (ref "U1") (pin "C21") (pinfunction "GND_C21") (pintype "power_in"))
      (node (ref "U1") (pin "C31") (pinfunction "GND_C31") (pintype "power_in"))
      (node (ref "U1") (pin "D18") (pinfunction "GND_D18") (pintype "power_in"))
      (node (ref "U1") (pin "D28") (pinfunction "GND_D28") (pintype "power_in"))
      (node (ref "U1") (pin "D8") (pinfunction "GND_D8") (pintype "power_in"))
      (node (ref "U1") (pin "E15") (pinfunction "GND_E15") (pintype "power_in"))
      (node (ref "U1") (pin "E25") (pinfunction "GND_E25") (pintype "power_in"))
      (node (ref "U1") (pin "E5") (pinfunction "GND_E5") (pintype "power_in"))
      (node (ref "U1") (pin "F12") (pinfunction "GND_F12") (pintype "power_in"))
      (node (ref "U1") (pin "F2") (pinfunction "GND_F2") (pintype "power_in"))
      (node (ref "U1") (pin "F22") (pinfunction "GND_F22") (pintype "power_in"))
      (node (ref "U1") (pin "F32") (pinfunction "GND_F32") (pintype "power_in"))
      (node (ref "U1") (pin "G19") (pinfunction "GND_G19") (pintype "power_in"))
      (node (ref "U1") (pin "G29") (pinfunction "GND_G29") (pintype "power_in"))
      (node (ref "U1") (pin "G9") (pinfunction "GND_G9") (pintype "power_in"))
      (node (ref "U1") (pin "H16") (pinfunction "GND_H16") (pintype "power_in"))
      (node (ref "U1") (pin "H26") (pinfunction "GND_H26") (pintype "power_in"))
      (node (ref "U1") (pin "H6") (pinfunction "GND_H6") (pintype "power_in"))
      (node (ref "U1") (pin "J13") (pinfunction "GND_J13") (pintype "power_in"))
      (node (ref "U1") (pin "J23") (pinfunction "GND_J23") (pintype "power_in"))
      (node (ref "U1") (pin "J3") (pinfunction "GND_J3") (pintype "power_in"))
      (node (ref "U1") (pin "J33") (pinfunction "GND_J33") (pintype "power_in"))
      (node (ref "U1") (pin "K10") (pinfunction "GND_K10") (pintype "power_in"))
      (node (ref "U1") (pin "K12") (pinfunction "GND_K12") (pintype "power_in"))
      (node (ref "U1") (pin "K20") (pinfunction "GND_K20") (pintype "power_in"))
      (node (ref "U1") (pin "K22") (pinfunction "GND_K22") (pintype "power_in"))
      (node (ref "U1") (pin "K30") (pinfunction "GND_K30") (pintype "power_in"))
      (node (ref "U1") (pin "L11") (pinfunction "GND_L11") (pintype "power_in"))
      (node (ref "U1") (pin "L13") (pinfunction "GND_L13") (pintype "power_in"))
      (node (ref "U1") (pin "L17") (pinfunction "GND_L17") (pintype "power_in"))
      (node (ref "U1") (pin "L21") (pinfunction "GND_L21") (pintype "power_in"))
      (node (ref "U1") (pin "L23") (pinfunction "GND_L23") (pintype "power_in"))
      (node (ref "U1") (pin "L27") (pinfunction "GND_L27") (pintype "power_in"))
      (node (ref "U1") (pin "L7") (pinfunction "GND_L7") (pintype "power_in"))
      (node (ref "U1") (pin "M12") (pinfunction "GND_M12") (pintype "power_in"))
      (node (ref "U1") (pin "M14") (pinfunction "GND_M14") (pintype "power_in"))
      (node (ref "U1") (pin "M22") (pinfunction "GND_M22") (pintype "power_in"))
      (node (ref "U1") (pin "M24") (pinfunction "GND_M24") (pintype "power_in"))
      (node (ref "U1") (pin "M34") (pinfunction "GND_M34") (pintype "power_in"))
      (node (ref "U1") (pin "M4") (pinfunction "GND_M4") (pintype "power_in"))
      (node (ref "U1") (pin "N1") (pinfunction "GND_N1") (pintype "power_in"))
      (node (ref "U1") (pin "N11") (pinfunction "GND_N11") (pintype "power_in"))
      (node (ref "U1") (pin "N21") (pinfunction "GND_N21") (pintype "power_in"))
      (node (ref "U1") (pin "N31") (pinfunction "GND_N31") (pintype "power_in"))
      (node (ref "U1") (pin "P16") (pinfunction "GND_P16") (pintype "power_in"))
      (node (ref "U1") (pin "P18") (pinfunction "GND_P18") (pintype "power_in"))
      (node (ref "U1") (pin "P28") (pinfunction "GND_P28") (pintype "power_in"))
      (node (ref "U1") (pin "P8") (pinfunction "GND_P8") (pintype "power_in"))
      (node (ref "U1") (pin "R13") (pinfunction "GND_R13") (pintype "power_in"))
      (node (ref "U1") (pin "R15") (pinfunction "GND_R15") (pintype "power_in"))
      (node (ref "U1") (pin "R25") (pinfunction "GND_R25") (pintype "power_in"))
      (node (ref "U1") (pin "R5") (pinfunction "GND_R5") (pintype "power_in"))
      (node (ref "U1") (pin "T12") (pinfunction "GND_T12") (pintype "power_in"))
      (node (ref "U1") (pin "T14") (pinfunction "GND_T14") (pintype "power_in"))
      (node (ref "U1") (pin "T2") (pinfunction "GND_T2") (pintype "power_in"))
      (node (ref "U1") (pin "T20") (pinfunction "GND_T20") (pintype "power_in"))
      (node (ref "U1") (pin "T22") (pinfunction "GND_T22") (pintype "power_in"))
      (node (ref "U1") (pin "T32") (pinfunction "GND_T32") (pintype "power_in"))
      (node (ref "U1") (pin "U19") (pinfunction "GND_U19") (pintype "power_in"))
      (node (ref "U1") (pin "U29") (pinfunction "GND_U29") (pintype "power_in"))
      (node (ref "U1") (pin "U9") (pinfunction "GND_U9") (pintype "power_in"))
      (node (ref "U1") (pin "V16") (pinfunction "GND_V16") (pintype "power_in"))
      (node (ref "U1") (pin "V26") (pinfunction "GND_V26") (pintype "power_in"))
      (node (ref "U1") (pin "V6") (pinfunction "GND_V6") (pintype "power_in"))
      (node (ref "U1") (pin "W13") (pinfunction "GND_W13") (pintype "power_in"))
      (node (ref "U1") (pin "W15") (pinfunction "GND_W15") (pintype "power_in"))
      (node (ref "U1") (pin "W23") (pinfunction "GND_W23") (pintype "power_in"))
      (node (ref "U1") (pin "W3") (pinfunction "GND_W3") (pintype "power_in"))
      (node (ref "U1") (pin "W33") (pinfunction "GND_W33") (pintype "power_in"))
      (node (ref "U1") (pin "Y10") (pinfunction "GND_Y10") (pintype "power_in"))
      (node (ref "U1") (pin "Y20") (pinfunction "GND_Y20") (pintype "power_in"))
      (node (ref "U1") (pin "Y22") (pinfunction "GND_Y22") (pintype "power_in"))
      (node (ref "U1") (pin "Y30") (pinfunction "GND_Y30") (pintype "power_in"))
    )
    (net (code "2") (name "VCC1V2") (class "Default")
      (node (ref "C158") (pin "1") (pinfunction "1_1") (pintype "passive"))
      (node (ref "C159") (pin "1") (pinfunction "1_1") (pintype "passive"))
      (node (ref "C160") (pin "1") (pinfunction "1_1") (pintype "passive"))
      (node (ref "C161") (pin "1") (pinfunction "1_1") (pintype "passive"))
      (node (ref "C162") (pin "1") (pinfunction "1_1") (pintype "passive"))
      (node (ref "C163") (pin "1") (pinfunction "1_1") (pintype "passive"))
      (node (ref "C164") (pin "1") (pinfunction "1_1") (pintype "passive"))
      (node (ref "C165") (pin "1") (pinfunction "1_1") (pintype "passive"))
      (node (ref "C166") (pin "1") (pinfunction "1_1") (pintype "passive"))
      (node (ref "C167") (pin "1") (pinfunction "1_1") (pintype "passive"))
      (node (ref "C168") (pin "1") (pinfunction "1_1") (pintype "passive"))
      (node (ref "C171") (pin "1") (pinfunction "1_1") (pintype "passive"))
      (node (ref "C175") (pin "1") (pinfunction "1_1") (pintype "passive"))
      (node (ref "C178") (pin "1") (pinfunction "1_1") (pintype "passive"))
      (node (ref "C179") (pin "1") (pinfunction "1_1") (pintype "passive"))
      (node (ref "C180") (pin "1") (pinfunction "1_1") (pintype "passive"))
      (node (ref "C181") (pin "1") (pinfunction "1_1") (pintype "passive"))
      (node (ref "C182") (pin "1") (pinfunction "1_1") (pintype "passive"))
      (node (ref "C183") (pin "1") (pinfunction "1_1") (pintype "passive"))
      (node (ref "C185") (pin "2") (pinfunction "2_2") (pintype "passive"))
      (node (ref "C186") (pin "2") (pinfunction "2_2") (pintype "passive"))
      (node (ref "C187") (pin "2") (pinfunction "2_2") (pintype "passive"))
      (node (ref "C188") (pin "2") (pinfunction "2_2") (pintype "passive"))
      (node (ref "C189") (pin "2") (pinfunction "2_2") (pintype "passive"))
      (node (ref "C190") (pin "2") (pinfunction "2_2") (pintype "passive"))
      (node (ref "C191") (pin "2") (pinfunction "2_2") (pintype "passive"))
      (node (ref "C192") (pin "2") (pinfunction "2_2") (pintype "passive"))
      (node (ref "C193") (pin "2") (pinfunction "2_2") (pintype "passive"))
      (node (ref "C194") (pin "2") (pinfunction "2_2") (pintype "passive"))
      (node (ref "C195") (pin "2") (pinfunction "2_2") (pintype "passive"))
      (node (ref "C196") (pin "2") (pinfunction "2_2") (pintype "passive"))
      (node (ref "C197") (pin "2") (pinfunction "2_2") (pintype "passive"))
      (node (ref "C198") (pin "2") (pinfunction "2_2") (pintype "passive"))
      (node (ref "C199") (pin "2") (pinfunction "2_2") (pintype "passive"))
      (node (ref "C200") (pin "2") (pinfunction "2_2") (pintype "passive"))
      (node (ref "C201") (pin "2") (pinfunction "2_2") (pintype "passive"))
      (node (ref "C202") (pin "2") (pinfunction "2_2") (pintype "passive"))
      (node (ref "C203") (pin "2") (pinfunction "2_2") (pintype "passive"))
      (node (ref "C204") (pin "2") (pinfunction "2_2") (pintype "passive"))
      (node (ref "C205") (pin "2") (pinfunction "2_2") (pintype "passive"))
      (node (ref "C206") (pin "2") (pinfunction "2_2") (pintype "passive"))
      (node (ref "C207") (pin "2") (pinfunction "2_2") (pintype "passive"))
      (node (ref "C208") (pin "2") (pinfunction "2_2") (pintype "passive"))
      (node (ref "C209") (pin "2") (pinfunction "2_2") (pintype "passive"))
      (node (ref "C210") (pin "2") (pinfunction "2_2") (pintype "passive"))
      (node (ref "C211") (pin "2") (pinfunction "2_2") (pintype "passive"))
      (node (ref "C212") (pin "2") (pinfunction "2_2") (pintype "passive"))
      (node (ref "C213") (pin "2") (pinfunction "2_2") (pintype "passive"))
      (node (ref "C214") (pin "2") (pinfunction "2_2") (pintype "passive"))
      (node (ref "C215") (pin "2") (pinfunction "2_2") (pintype "passive"))
      (node (ref "C216") (pin "2") (pinfunction "2_2") (pintype "passive"))
      (node (ref "C217") (pin "2") (pinfunction "2_2") (pintype "passive"))
      (node (ref "C218") (pin "2") (pinfunction "2_2") (pintype "passive"))
      (node (ref "C219") (pin "2") (pinfunction "2_2") (pintype "passive"))
      (node (ref "C220") (pin "2") (pinfunction "2_2") (pintype "passive"))
      (node (ref "C221") (pin "2") (pinfunction "2_2") (pintype "passive"))
      (node (ref "C222") (pin "2") (pinfunction "2_2") (pintype "passive"))
      (node (ref "C223") (pin "2") (pinfunction "2_2") (pintype "passive"))
      (node (ref "C224") (pin "2") (pinfunction "2_2") (pintype "passive"))
      (node (ref "C225") (pin "2") (pinfunction "2_2") (pintype "passive"))
      (node (ref "C226") (pin "2") (pinfunction "2_2") (pintype "passive"))
      (node (ref "C227") (pin "2") (pinfunction "2_2") (pintype "passive"))
      (node (ref "C228") (pin "2") (pinfunction "2_2") (pintype "passive"))
      (node (ref "C229") (pin "2") (pinfunction "2_2") (pintype "passive"))
      (node (ref "C230") (pin "2") (pinfunction "2_2") (pintype "passive"))
      (node (ref "C231") (pin "2") (pinfunction "2_2") (pintype "passive"))
      (node (ref "C232") (pin "2") (pinfunction "2_2") (pintype "passive"))
      (node (ref "C233") (pin "2") (pinfunction "2_2") (pintype "passive"))
      (node (ref "C234") (pin "2") (pinfunction "2_2") (pintype "passive"))
      (node (ref "C235") (pin "1") (pinfunction "1_1") (pintype "passive"))
      (node (ref "U1") (pin "AA16") (pinfunction "VCCINT_AA16") (pintype "power_in"))
      (node (ref "U1") (pin "AA18") (pinfunction "VCCINT_AA18") (pintype "power_in"))
      (node (ref "U1") (pin "AA20") (pinfunction "VCCINT_AA20") (pintype "power_in"))
      (node (ref "U1") (pin "AB11") (pinfunction "VCCINT_AB11") (pintype "power_in"))
      (node (ref "U1") (pin "AB21") (pinfunction "VCCINT_AB21") (pintype "power_in"))
      (node (ref "U1") (pin "AB7") (pinfunction "VCCINT_AB7") (pintype "power_in"))
      (node (ref "U1") (pin "AC12") (pinfunction "VCCINT_AC12") (pintype "power_in"))
      (node (ref "U1") (pin "AC14") (pinfunction "VCCINT_AC14") (pintype "power_in"))
      (node (ref "U1") (pin "AC18") (pinfunction "VCCINT_AC18") (pintype "power_in"))
      (node (ref "U1") (pin "AC20") (pinfunction "VCCINT_AC20") (pintype "power_in"))
      (node (ref "U1") (pin "AC22") (pinfunction "VCCINT_AC22") (pintype "power_in"))
      (node (ref "U1") (pin "AD13") (pinfunction "VCCINT_AD13") (pintype "power_in"))
      (node (ref "U1") (pin "AD15") (pinfunction "VCCINT_AD15") (pintype "power_in"))
      (node (ref "U1") (pin "AD23") (pinfunction "VCCINT_AD23") (pintype "power_in"))
      (node (ref "U1") (pin "AD25") (pinfunction "VCCINT_AD25") (pintype "power_in"))
      (node (ref "U1") (pin "AE12") (pinfunction "VCCINT_AE12") (pintype "power_in"))
      (node (ref "U1") (pin "AE14") (pinfunction "VCCINT_AE14") (pintype "power_in"))
      (node (ref "U1") (pin "AE22") (pinfunction "VCCINT_AE22") (pintype "power_in"))
      (node (ref "U1") (pin "AE24") (pinfunction "VCCINT_AE24") (pintype "power_in"))
      (node (ref "U1") (pin "AE28") (pinfunction "VCCINT_AE28") (pintype "power_in"))
      (node (ref "U1") (pin "AF13") (pinfunction "VCCINT_AF13") (pintype "power_in"))
      (node (ref "U1") (pin "AF19") (pinfunction "VCCINT_AF19") (pintype "power_in"))
      (node (ref "U1") (pin "AF23") (pinfunction "VCCINT_AF23") (pintype "power_in"))
      (node (ref "U1") (pin "AF9") (pinfunction "VCCINT_AF9") (pintype "power_in"))
      (node (ref "U1") (pin "AH13") (pinfunction "VCCINT_AH13") (pintype "power_in"))
      (node (ref "U1") (pin "AH15") (pinfunction "VCCINT_AH15") (pintype "power_in"))
      (node (ref "U1") (pin "G20") (pinfunction "VCCINT_G20") (pintype "power_in"))
      (node (ref "U1") (pin "G22") (pinfunction "VCCINT_G22") (pintype "power_in"))
      (node (ref "U1") (pin "J12") (pinfunction "VCCINT_J12") (pintype "power_in"))
      (node (ref "U1") (pin "J16") (pinfunction "VCCINT_J16") (pintype "power_in"))
      (node (ref "U1") (pin "J22") (pinfunction "VCCINT_J22") (pintype "power_in"))
      (node (ref "U1") (pin "J26") (pinfunction "VCCINT_J26") (pintype "power_in"))
      (node (ref "U1") (pin "K11") (pinfunction "VCCINT_K11") (pintype "power_in"))
      (node (ref "U1") (pin "K13") (pinfunction "VCCINT_K13") (pintype "power_in"))
      (node (ref "U1") (pin "K21") (pinfunction "VCCINT_K21") (pintype "power_in"))
      (node (ref "U1") (pin "K23") (pinfunction "VCCINT_K23") (pintype "power_in"))
      (node (ref "U1") (pin "K7") (pinfunction "VCCINT_K7") (pintype "power_in"))
      (node (ref "U1") (pin "L10") (pinfunction "VCCINT_L10") (pintype "power_in"))
      (node (ref "U1") (pin "L12") (pinfunction "VCCINT_L12") (pintype "power_in"))
      (node (ref "U1") (pin "L20") (pinfunction "VCCINT_L20") (pintype "power_in"))
      (node (ref "U1") (pin "L22") (pinfunction "VCCINT_L22") (pintype "power_in"))
      (node (ref "U1") (pin "M13") (pinfunction "VCCINT_M13") (pintype "power_in"))
      (node (ref "U1") (pin "M15") (pinfunction "VCCINT_M15") (pintype "power_in"))
      (node (ref "U1") (pin "M21") (pinfunction "VCCINT_M21") (pintype "power_in"))
      (node (ref "U1") (pin "M23") (pinfunction "VCCINT_M23") (pintype "power_in"))
      (node (ref "U1") (pin "N14") (pinfunction "VCCINT_N14") (pintype "power_in"))
      (node (ref "U1") (pin "N24") (pinfunction "VCCINT_N24") (pintype "power_in"))
      (node (ref "U1") (pin "N28") (pinfunction "VCCINT_N28") (pintype "power_in"))
      (node (ref "U1") (pin "P15") (pinfunction "VCCINT_P15") (pintype "power_in"))
      (node (ref "U1") (pin "P17") (pinfunction "VCCINT_P17") (pintype "power_in"))
      (node (ref "U1") (pin "P19") (pinfunction "VCCINT_P19") (pintype "power_in"))
      (node (ref "U1") (pin "R12") (pinfunction "VCCINT_R12") (pintype "power_in"))
      (node (ref "U1") (pin "R14") (pinfunction "VCCINT_R14") (pintype "power_in"))
      (node (ref "U1") (pin "R16") (pinfunction "VCCINT_R16") (pintype "power_in"))
      (node (ref "U1") (pin "T13") (pinfunction "VCCINT_T13") (pintype "power_in"))
      (node (ref "U1") (pin "T15") (pinfunction "VCCINT_T15") (pintype "power_in"))
      (node (ref "U1") (pin "T19") (pinfunction "VCCINT_T19") (pintype "power_in"))
      (node (ref "U1") (pin "T21") (pinfunction "VCCINT_T21") (pintype "power_in"))
      (node (ref "U1") (pin "U18") (pinfunction "VCCINT_U18") (pintype "power_in"))
      (node (ref "U1") (pin "U20") (pinfunction "VCCINT_U20") (pintype "power_in"))
      (node (ref "U1") (pin "V15") (pinfunction "VCCINT_V15") (pintype "power_in"))
      (node (ref "U1") (pin "V17") (pinfunction "VCCINT_V17") (pintype "power_in"))
      (node (ref "U1") (pin "W14") (pinfunction "VCCINT_W14") (pintype "power_in"))
      (node (ref "U1") (pin "W16") (pinfunction "VCCINT_W16") (pintype "power_in"))
      (node (ref "U1") (pin "W22") (pinfunction "VCCINT_W22") (pintype "power_in"))
      (node (ref "U1") (pin "Y19") (pinfunction "VCCINT_Y19") (pintype "power_in"))
      (node (ref "U1") (pin "Y21") (pinfunction "VCCINT_Y21") (pintype "power_in"))
      (node (ref "U1") (pin "Y23") (pinfunction "VCCINT_Y23") (pintype "power_in"))
    )
    (net (code "3") (name "VCC2V5") (class "Default")
      (node (ref "C100") (pin "2") (pinfunction "2_2") (pintype "passive"))
      (node (ref "C101") (pin "2") (pinfunction "2_2") (pintype "passive"))
      (node (ref "C102") (pin "2") (pinfunction "2_2") (pintype "passive"))
      (node (ref "C103") (pin "2") (pinfunction "2_2") (pintype "passive"))
      (node (ref "C104") (pin "2") (pinfunction "2_2") (pintype "passive"))
      (node (ref "C105") (pin "2") (pinfunction "2_2") (pintype "passive"))
      (node (ref "C106") (pin "2") (pinfunction "2_2") (pintype "passive"))
      (node (ref "C107") (pin "2") (pinfunction "2_2") (pintype "passive"))
      (node (ref "C108") (pin "2") (pinfunction "2_2") (pintype "passive"))
      (node (ref "C109") (pin "2") (pinfunction "2_2") (pintype "passive"))
      (node (ref "C110") (pin "2") (pinfunction "2_2") (pintype "passive"))
      (node (ref "C111") (pin "2") (pinfunction "2_2") (pintype "passive"))
      (node (ref "C130") (pin "2") (pinfunction "2_2") (pintype "passive"))
      (node (ref "C131") (pin "2") (pinfunction "2_2") (pintype "passive"))
      (node (ref "C132") (pin "2") (pinfunction "2_2") (pintype "passive"))
      (node (ref "C133") (pin "2") (pinfunction "2_2") (pintype "passive"))
      (node (ref "C134") (pin "2") (pinfunction "2_2") (pintype "passive"))
      (node (ref "C135") (pin "2") (pinfunction "2_2") (pintype "passive"))
      (node (ref "C136") (pin "2") (pinfunction "2_2") (pintype "passive"))
      (node (ref "C137") (pin "2") (pinfunction "2_2") (pintype "passive"))
      (node (ref "C138") (pin "2") (pinfunction "2_2") (pintype "passive"))
      (node (ref "C139") (pin "2") (pinfunction "2_2") (pintype "passive"))
      (node (ref "C140") (pin "2") (pinfunction "2_2") (pintype "passive"))
      (node (ref "C141") (pin "2") (pinfunction "2_2") (pintype "passive"))
      (node (ref "C142") (pin "2") (pinfunction "2_2") (pintype "passive"))
      (node (ref "C143") (pin "2") (pinfunction "2_2") (pintype "passive"))
      (node (ref "C144") (pin "2") (pinfunction "2_2") (pintype "passive"))
      (node (ref "C145") (pin "2") (pinfunction "2_2") (pintype "passive"))
      (node (ref "C146") (pin "2") (pinfunction "2_2") (pintype "passive"))
      (node (ref "C147") (pin "2") (pinfunction "2_2") (pintype "passive"))
      (node (ref "C148") (pin "1") (pinfunction "1_1") (pintype "passive"))
      (node (ref "C46") (pin "1") (pinfunction "1_1") (pintype "passive"))
      (node (ref "C47") (pin "1") (pinfunction "1_1") (pintype "passive"))
      (node (ref "C48") (pin "1") (pinfunction "1_1") (pintype "passive"))
      (node (ref "C49") (pin "1") (pinfunction "1_1") (pintype "passive"))
      (node (ref "C50") (pin "1") (pinfunction "1_1") (pintype "passive"))
      (node (ref "C51") (pin "1") (pinfunction "1_1") (pintype "passive"))
      (node (ref "C52") (pin "1") (pinfunction "1_1") (pintype "passive"))
      (node (ref "C53") (pin "1") (pinfunction "1_1") (pintype "passive"))
      (node (ref "C54") (pin "1") (pinfunction "1_1") (pintype "passive"))
      (node (ref "C55") (pin "1") (pinfunction "1_1") (pintype "passive"))
      (node (ref "C56") (pin "1") (pinfunction "1_1") (pintype "passive"))
      (node (ref "C57") (pin "1") (pinfunction "1_1") (pintype "passive"))
      (node (ref "C58") (pin "1") (pinfunction "1_1") (pintype "passive"))
      (node (ref "C59") (pin "1") (pinfunction "1_1") (pintype "passive"))
      (node (ref "C60") (pin "1") (pinfunction "1_1") (pintype "passive"))
      (node (ref "C61") (pin "1") (pinfunction "1_1") (pintype "passive"))
      (node (ref "C62") (pin "1") (pinfunction "1_1") (pintype "passive"))
      (node (ref "C63") (pin "1") (pinfunction "1_1") (pintype "passive"))
      (node (ref "C64") (pin "1") (pinfunction "1_1") (pintype "passive"))
      (node (ref "C65") (pin "1") (pinfunction "1_1") (pintype "passive"))
      (node (ref "C66") (pin "1") (pinfunction "1_1") (pintype "passive"))
      (node (ref "C67") (pin "2") (pinfunction "2_2") (pintype "passive"))
      (node (ref "C68") (pin "2") (pinfunction "2_2") (pintype "passive"))
      (node (ref "C69") (pin "2") (pinfunction "2_2") (pintype "passive"))
      (node (ref "C70") (pin "2") (pinfunction "2_2") (pintype "passive"))
      (node (ref "C71") (pin "2") (pinfunction "2_2") (pintype "passive"))
      (node (ref "C72") (pin "2") (pinfunction "2_2") (pintype "passive"))
      (node (ref "C73") (pin "2") (pinfunction "2_2") (pintype "passive"))
      (node (ref "C74") (pin "2") (pinfunction "2_2") (pintype "passive"))
      (node (ref "C75") (pin "2") (pinfunction "2_2") (pintype "passive"))
      (node (ref "C76") (pin "2") (pinfunction "2_2") (pintype "passive"))
      (node (ref "C77") (pin "2") (pinfunction "2_2") (pintype "passive"))
      (node (ref "C78") (pin "2") (pinfunction "2_2") (pintype "passive"))
      (node (ref "C79") (pin "2") (pinfunction "2_2") (pintype "passive"))
      (node (ref "C80") (pin "2") (pinfunction "2_2") (pintype "passive"))
      (node (ref "C81") (pin "2") (pinfunction "2_2") (pintype "passive"))
      (node (ref "C82") (pin "2") (pinfunction "2_2") (pintype "passive"))
      (node (ref "C83") (pin "2") (pinfunction "2_2") (pintype "passive"))
      (node (ref "C84") (pin "2") (pinfunction "2_2") (pintype "passive"))
      (node (ref "C85") (pin "2") (pinfunction "2_2") (pintype "passive"))
      (node (ref "C86") (pin "2") (pinfunction "2_2") (pintype "passive"))
      (node (ref "C87") (pin "2") (pinfunction "2_2") (pintype "passive"))
      (node (ref "C88") (pin "2") (pinfunction "2_2") (pintype "passive"))
      (node (ref "C89") (pin "2") (pinfunction "2_2") (pintype "passive"))
      (node (ref "C90") (pin "2") (pinfunction "2_2") (pintype "passive"))
      (node (ref "C91") (pin "2") (pinfunction "2_2") (pintype "passive"))
      (node (ref "C92") (pin "2") (pinfunction "2_2") (pintype "passive"))
      (node (ref "C93") (pin "2") (pinfunction "2_2") (pintype "passive"))
      (node (ref "C94") (pin "2") (pinfunction "2_2") (pintype "passive"))
      (node (ref "C95") (pin "2") (pinfunction "2_2") (pintype "passive"))
      (node (ref "C96") (pin "2") (pinfunction "2_2") (pintype "passive"))
      (node (ref "C97") (pin "2") (pinfunction "2_2") (pintype "passive"))
      (node (ref "C98") (pin "2") (pinfunction "2_2") (pintype "passive"))
      (node (ref "C99") (pin "2") (pinfunction "2_2") (pintype "passive"))
      (node (ref "U1") (pin "AA10") (pinfunction "VCCAUX_AA10") (pintype "power_in"))
      (node (ref "U1") (pin "AB27") (pinfunction "VCCAUX_AB27") (pintype "power_in"))
      (node (ref "U1") (pin "AC24") (pinfunction "VCCAUX_AC24") (pintype "power_in"))
      (node (ref "U1") (pin "AD11") (pinfunction "VCCAUX_AD11") (pintype "power_in"))
      (node (ref "U1") (pin "AF25") (pinfunction "VCCAUX_AF25") (pintype "power_in"))
      (node (ref "U1") (pin "AG12") (pinfunction "VCCAUX_AG12") (pintype "power_in"))
      (node (ref "U1") (pin "AH9") (pinfunction "VCCAUX_AH9") (pintype "power_in"))
      (node (ref "U1") (pin "AJ16") (pinfunction "VCCAUX_AJ16") (pintype "power_in"))
      (node (ref "U1") (pin "AJ26") (pinfunction "VCCAUX_AJ26") (pintype "power_in"))
      (node (ref "U1") (pin "AP19") (pinfunction "AVDD_SM_AP19") (pintype "input"))
      (node (ref "U1") (pin "B16") (pinfunction "AVDD_ADC_B16") (pintype "input"))
      (node (ref "U1") (pin "F19") (pinfunction "VCCAUX_F19") (pintype "power_in"))
      (node (ref "U1") (pin "F9") (pinfunction "VCCAUX_F9") (pintype "power_in"))
      (node (ref "U1") (pin "G26") (pinfunction "VCCAUX_G26") (pintype "power_in"))
      (node (ref "U1") (pin "H23") (pinfunction "VCCAUX_H23") (pintype "power_in"))
      (node (ref "U1") (pin "J10") (pinfunction "VCCAUX_J10") (pintype "power_in"))
      (node (ref "U1") (pin "L24") (pinfunction "VCCAUX_L24") (pintype "power_in"))
      (node (ref "U1") (pin "M11") (pinfunction "VCCAUX_M11") (pintype "power_in"))
      (node (ref "U1") (pin "N8") (pinfunction "VCCAUX_N8") (pintype "power_in"))
      (node (ref "U1") (pin "P25") (pinfunction "VCCAUX_P25") (pintype "power_in"))
      (node (ref "U1") (pin "R18") (pinfunction "VCCAUX_R18") (pintype "power_in"))
      (node (ref "U1") (pin "T9") (pinfunction "VCCAUX_T9") (pintype "power_in"))
      (node (ref "U1") (pin "U16") (pinfunction "VCCAUX_U16") (pintype "power_in"))
      (node (ref "U1") (pin "V19") (pinfunction "VCCAUX_V19") (pintype "power_in"))
      (node (ref "U1") (pin "W26") (pinfunction "VCCAUX_W26") (pintype "power_in"))
      (node (ref "U1") (pin "Y17") (pinfunction "VCCAUX_Y17") (pintype "power_in"))
    )
    (net (code "4") (name "VCC3V3") (class "Default")
      (node (ref "C112") (pin "1") (pinfunction "1_1") (pintype "passive"))
      (node (ref "C113") (pin "1") (pinfunction "1_1") (pintype "passive"))
      (node (ref "C114") (pin "1") (pinfunction "1_1") (pintype "passive"))
      (node (ref "C115") (pin "1") (pinfunction "1_1") (pintype "passive"))
      (node (ref "C116") (pin "1") (pinfunction "1_1") (pintype "passive"))
      (node (ref "C117") (pin "1") (pinfunction "1_1") (pintype "passive"))
      (node (ref "C118") (pin "1") (pinfunction "1_1") (pintype "passive"))
      (node (ref "C119") (pin "1") (pinfunction "1_1") (pintype "passive"))
      (node (ref "C120") (pin "1") (pinfunction "1_1") (pintype "passive"))
      (node (ref "C121") (pin "2") (pinfunction "2_2") (pintype "passive"))
      (node (ref "C122") (pin "2") (pinfunction "2_2") (pintype "passive"))
      (node (ref "C123") (pin "2") (pinfunction "2_2") (pintype "passive"))
      (node (ref "C124") (pin "2") (pinfunction "2_2") (pintype "passive"))
      (node (ref "C125") (pin "2") (pinfunction "2_2") (pintype "passive"))
      (node (ref "C126") (pin "2") (pinfunction "2_2") (pintype "passive"))
      (node (ref "C127") (pin "2") (pinfunction "2_2") (pintype "passive"))
      (node (ref "C128") (pin "2") (pinfunction "2_2") (pintype "passive"))
      (node (ref "C129") (pin "2") (pinfunction "2_2") (pintype "passive"))
      (node (ref "C149") (pin "2") (pinfunction "2_2") (pintype "passive"))
      (node (ref "C150") (pin "2") (pinfunction "2_2") (pintype "passive"))
      (node (ref "C151") (pin "2") (pinfunction "2_2") (pintype "passive"))
      (node (ref "C152") (pin "2") (pinfunction "2_2") (pintype "passive"))
      (node (ref "C153") (pin "2") (pinfunction "2_2") (pintype "passive"))
      (node (ref "C154") (pin "2") (pinfunction "2_2") (pintype "passive"))
      (node (ref "C155") (pin "2") (pinfunction "2_2") (pintype "passive"))
      (node (ref "C156") (pin "2") (pinfunction "2_2") (pintype "passive"))
      (node (ref "C157") (pin "2") (pinfunction "2_2") (pintype "passive"))
      (node (ref "C169") (pin "2") (pinfunction "2_2") (pintype "passive"))
      (node (ref "C170") (pin "2") (pinfunction "2_2") (pintype "passive"))
      (node (ref "C172") (pin "2") (pinfunction "2_2") (pintype "passive"))
      (node (ref "C173") (pin "2") (pinfunction "2_2") (pintype "passive"))
      (node (ref "C174") (pin "2") (pinfunction "2_2") (pintype "passive"))
      (node (ref "C176") (pin "2") (pinfunction "2_2") (pintype "passive"))
      (node (ref "C177") (pin "2") (pinfunction "2_2") (pintype "passive"))
      (node (ref "C184") (pin "1") (pinfunction "1_1") (pintype "passive"))
    )
  )
)
